# R211X.net
KiCad netlist of a schematic drawn in EAGLE
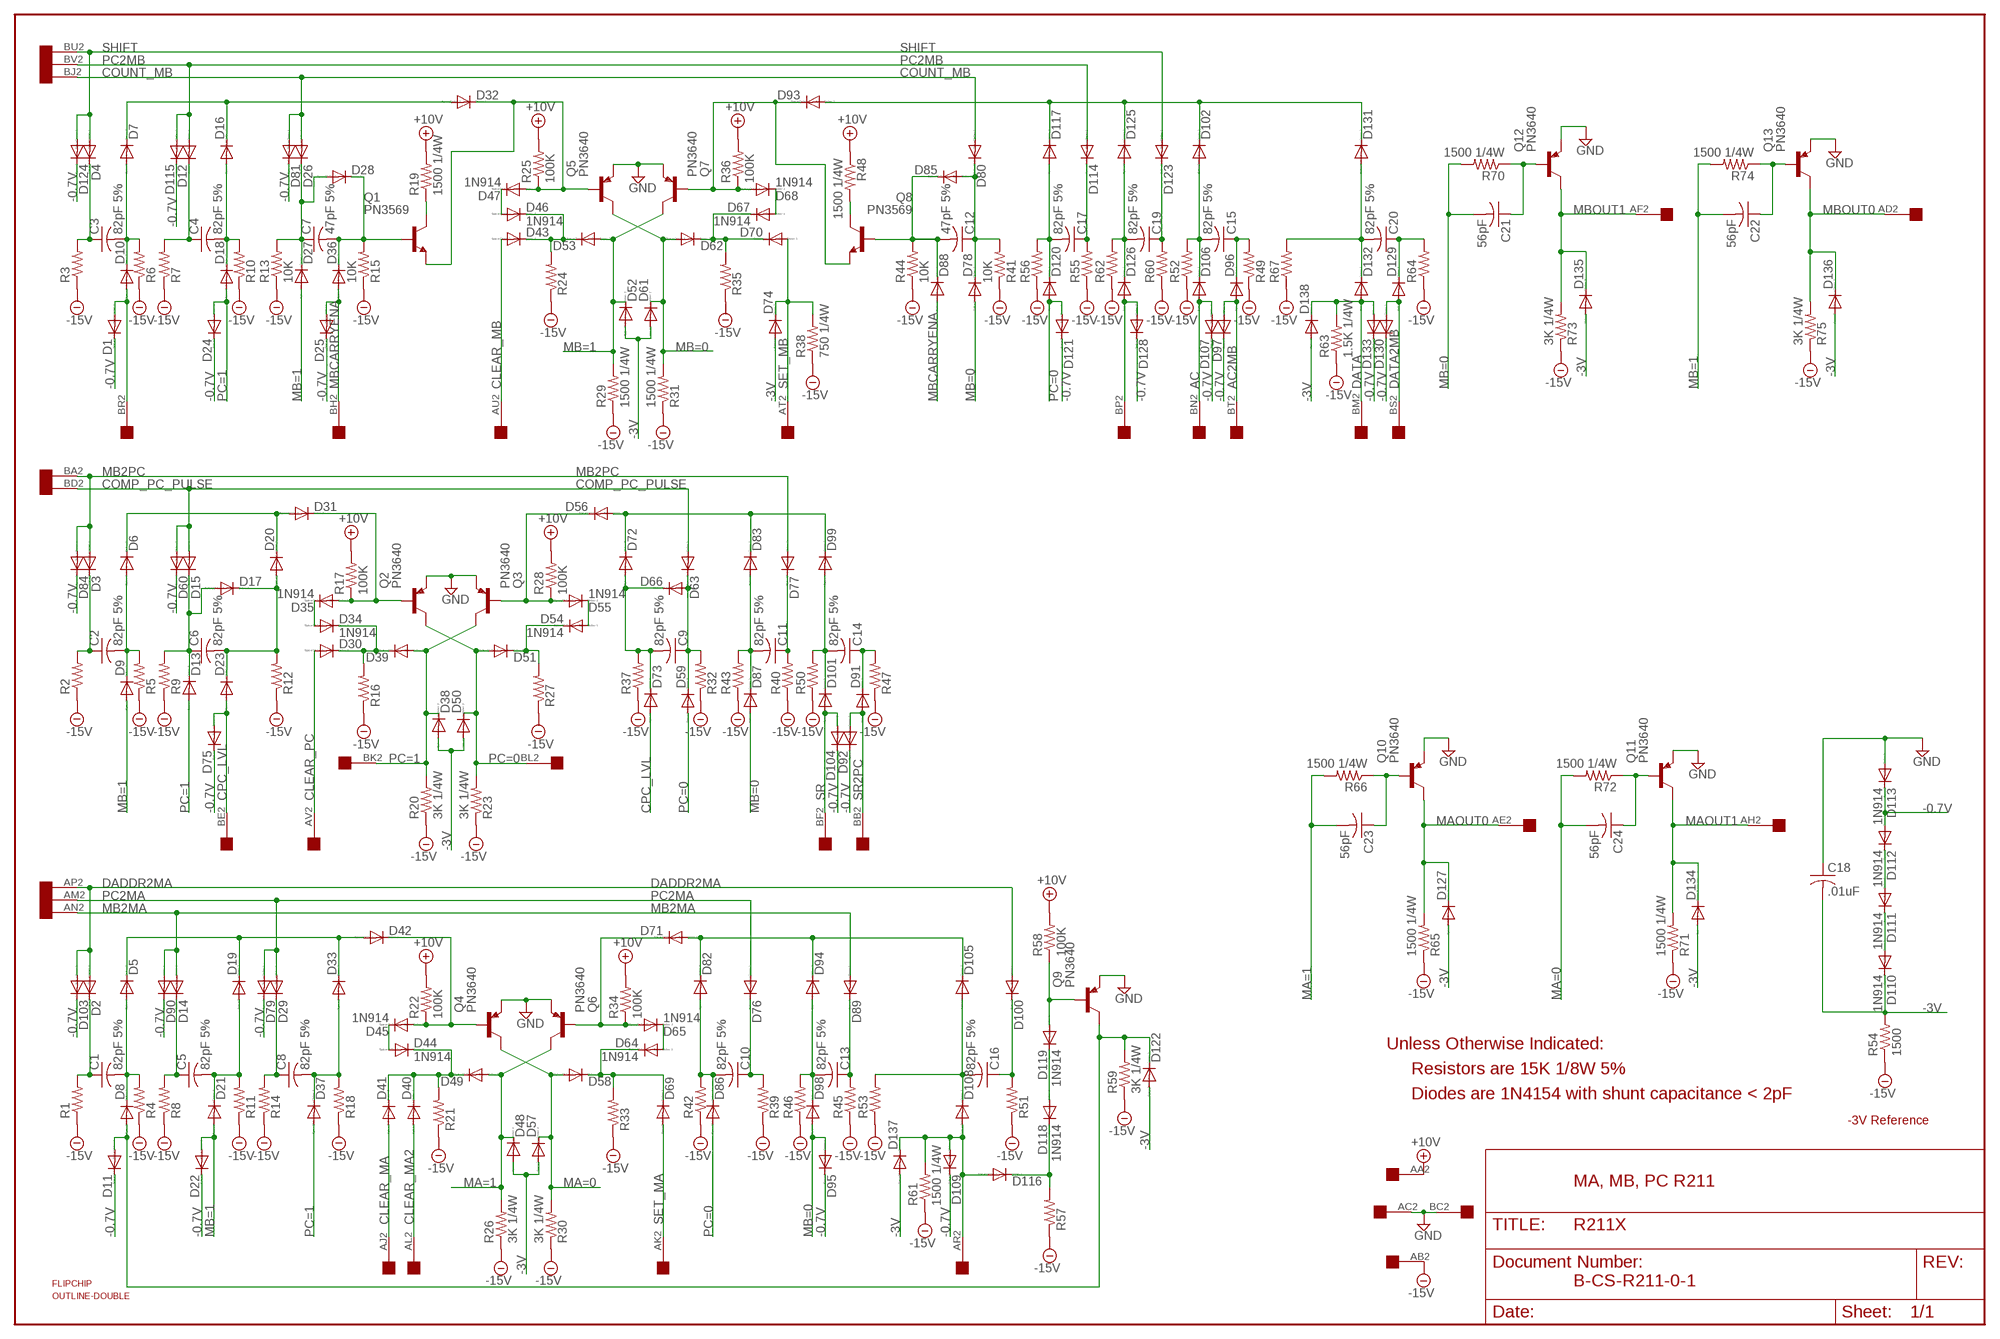
[diagram p0: schematic, sheet 1]

(export (version "E")
  (design (tool "Eeschema 10.0.6"))
  (components
    (comp (ref "C1")
      (value "82pF 5%")
      (footprint "eagle-import:C050-025X075")
      (libsource (lib "eagle-import") (part "C-US050-025X075"))
    )
    (comp (ref "C2")
      (value "82pF 5%")
      (footprint "eagle-import:C050-025X075")
      (libsource (lib "eagle-import") (part "C-US050-025X075"))
    )
    (comp (ref "C3")
      (value "82pF 5%")
      (footprint "eagle-import:C050-025X075")
      (libsource (lib "eagle-import") (part "C-US050-025X075"))
    )
    (comp (ref "C4")
      (value "82pF 5%")
      (footprint "eagle-import:C050-025X075")
      (libsource (lib "eagle-import") (part "C-US050-025X075"))
    )
    (comp (ref "C5")
      (value "82pF 5%")
      (footprint "eagle-import:C050-025X075")
      (libsource (lib "eagle-import") (part "C-US050-025X075"))
    )
    (comp (ref "C6")
      (value "82pF 5%")
      (footprint "eagle-import:C050-025X075")
      (libsource (lib "eagle-import") (part "C-US050-025X075"))
    )
    (comp (ref "C7")
      (value "47pF 5%")
      (footprint "eagle-import:C050-025X075")
      (libsource (lib "eagle-import") (part "C-US050-025X075"))
    )
    (comp (ref "C8")
      (value "82pF 5%")
      (footprint "eagle-import:C050-025X075")
      (libsource (lib "eagle-import") (part "C-US050-025X075"))
    )
    (comp (ref "C9")
      (value "82pF 5%")
      (footprint "eagle-import:C050-025X075")
      (libsource (lib "eagle-import") (part "C-US050-025X075"))
    )
    (comp (ref "C10")
      (value "82pF 5%")
      (footprint "eagle-import:C050-025X075")
      (libsource (lib "eagle-import") (part "C-US050-025X075"))
    )
    (comp (ref "C11")
      (value "82pF 5%")
      (footprint "eagle-import:C050-025X075")
      (libsource (lib "eagle-import") (part "C-US050-025X075"))
    )
    (comp (ref "C12")
      (value "47pF 5%")
      (footprint "eagle-import:C050-025X075")
      (libsource (lib "eagle-import") (part "C-US050-025X075"))
    )
    (comp (ref "C13")
      (value "82pF 5%")
      (footprint "eagle-import:C050-025X075")
      (libsource (lib "eagle-import") (part "C-US050-025X075"))
    )
    (comp (ref "C14")
      (value "82pF 5%")
      (footprint "eagle-import:C050-025X075")
      (libsource (lib "eagle-import") (part "C-US050-025X075"))
    )
    (comp (ref "C15")
      (value "82pF 5%")
      (footprint "eagle-import:C050-025X075")
      (libsource (lib "eagle-import") (part "C-US050-025X075"))
    )
    (comp (ref "C16")
      (value "82pF 5%")
      (footprint "eagle-import:C050-025X075")
      (libsource (lib "eagle-import") (part "C-US050-025X075"))
    )
    (comp (ref "C17")
      (value "82pF 5%")
      (footprint "eagle-import:C050-025X075")
      (libsource (lib "eagle-import") (part "C-US050-025X075"))
    )
    (comp (ref "C18")
      (value ".01uF")
      (footprint "eagle-import:C050-025X075")
      (libsource (lib "eagle-import") (part "C-US050-025X075"))
    )
    (comp (ref "C19")
      (value "82pF 5%")
      (footprint "eagle-import:C050-025X075")
      (libsource (lib "eagle-import") (part "C-US050-025X075"))
    )
    (comp (ref "C20")
      (value "82pF 5%")
      (footprint "eagle-import:C050-025X075")
      (libsource (lib "eagle-import") (part "C-US050-025X075"))
    )
    (comp (ref "C21")
      (value "56pF")
      (footprint "eagle-import:C050-025X075")
      (libsource (lib "eagle-import") (part "C-US050-025X075"))
    )
    (comp (ref "C22")
      (value "56pF")
      (footprint "eagle-import:C050-025X075")
      (libsource (lib "eagle-import") (part "C-US050-025X075"))
    )
    (comp (ref "C23")
      (value "56pF")
      (footprint "eagle-import:C050-025X075")
      (libsource (lib "eagle-import") (part "C-US050-025X075"))
    )
    (comp (ref "C24")
      (value "56pF")
      (footprint "eagle-import:C050-025X075")
      (libsource (lib "eagle-import") (part "C-US050-025X075"))
    )
    (comp (ref "D1")
      (value "1N4148DO35-10")
      (footprint "eagle-import:DO35-10")
      (libsource (lib "eagle-import") (part "1N4148DO35-10"))
    )
    (comp (ref "D2")
      (value "1N4148DO35-10")
      (footprint "eagle-import:DO35-10")
      (libsource (lib "eagle-import") (part "1N4148DO35-10"))
    )
    (comp (ref "D3")
      (value "1N4148DO35-10")
      (footprint "eagle-import:DO35-10")
      (libsource (lib "eagle-import") (part "1N4148DO35-10"))
    )
    (comp (ref "D4")
      (value "1N4148DO35-10")
      (footprint "eagle-import:DO35-10")
      (libsource (lib "eagle-import") (part "1N4148DO35-10"))
    )
    (comp (ref "D5")
      (value "1N4148DO35-10")
      (footprint "eagle-import:DO35-10")
      (libsource (lib "eagle-import") (part "1N4148DO35-10"))
    )
    (comp (ref "D6")
      (value "1N4148DO35-10")
      (footprint "eagle-import:DO35-10")
      (libsource (lib "eagle-import") (part "1N4148DO35-10"))
    )
    (comp (ref "D7")
      (value "1N4148DO35-10")
      (footprint "eagle-import:DO35-10")
      (libsource (lib "eagle-import") (part "1N4148DO35-10"))
    )
    (comp (ref "D8")
      (value "1N4148DO35-10")
      (footprint "eagle-import:DO35-10")
      (libsource (lib "eagle-import") (part "1N4148DO35-10"))
    )
    (comp (ref "D9")
      (value "1N4148DO35-10")
      (footprint "eagle-import:DO35-10")
      (libsource (lib "eagle-import") (part "1N4148DO35-10"))
    )
    (comp (ref "D10")
      (value "1N4148DO35-10")
      (footprint "eagle-import:DO35-10")
      (libsource (lib "eagle-import") (part "1N4148DO35-10"))
    )
    (comp (ref "D11")
      (value "1N4148DO35-10")
      (footprint "eagle-import:DO35-10")
      (libsource (lib "eagle-import") (part "1N4148DO35-10"))
    )
    (comp (ref "D12")
      (value "1N4148DO35-10")
      (footprint "eagle-import:DO35-10")
      (libsource (lib "eagle-import") (part "1N4148DO35-10"))
    )
    (comp (ref "D13")
      (value "1N4148DO35-10")
      (footprint "eagle-import:DO35-10")
      (libsource (lib "eagle-import") (part "1N4148DO35-10"))
    )
    (comp (ref "D14")
      (value "1N4148DO35-10")
      (footprint "eagle-import:DO35-10")
      (libsource (lib "eagle-import") (part "1N4148DO35-10"))
    )
    (comp (ref "D15")
      (value "1N4148DO35-10")
      (footprint "eagle-import:DO35-10")
      (libsource (lib "eagle-import") (part "1N4148DO35-10"))
    )
    (comp (ref "D16")
      (value "1N4148DO35-10")
      (footprint "eagle-import:DO35-10")
      (libsource (lib "eagle-import") (part "1N4148DO35-10"))
    )
    (comp (ref "D17")
      (value "1N4148DO35-10")
      (footprint "eagle-import:DO35-10")
      (libsource (lib "eagle-import") (part "1N4148DO35-10"))
    )
    (comp (ref "D18")
      (value "1N4148DO35-10")
      (footprint "eagle-import:DO35-10")
      (libsource (lib "eagle-import") (part "1N4148DO35-10"))
    )
    (comp (ref "D19")
      (value "1N4148DO35-10")
      (footprint "eagle-import:DO35-10")
      (libsource (lib "eagle-import") (part "1N4148DO35-10"))
    )
    (comp (ref "D20")
      (value "1N4148DO35-10")
      (footprint "eagle-import:DO35-10")
      (libsource (lib "eagle-import") (part "1N4148DO35-10"))
    )
    (comp (ref "D21")
      (value "1N4148DO35-10")
      (footprint "eagle-import:DO35-10")
      (libsource (lib "eagle-import") (part "1N4148DO35-10"))
    )
    (comp (ref "D22")
      (value "1N4148DO35-10")
      (footprint "eagle-import:DO35-10")
      (libsource (lib "eagle-import") (part "1N4148DO35-10"))
    )
    (comp (ref "D23")
      (value "1N4148DO35-10")
      (footprint "eagle-import:DO35-10")
      (libsource (lib "eagle-import") (part "1N4148DO35-10"))
    )
    (comp (ref "D24")
      (value "1N4148DO35-10")
      (footprint "eagle-import:DO35-10")
      (libsource (lib "eagle-import") (part "1N4148DO35-10"))
    )
    (comp (ref "D25")
      (value "1N4148DO35-10")
      (footprint "eagle-import:DO35-10")
      (libsource (lib "eagle-import") (part "1N4148DO35-10"))
    )
    (comp (ref "D26")
      (value "1N4148DO35-10")
      (footprint "eagle-import:DO35-10")
      (libsource (lib "eagle-import") (part "1N4148DO35-10"))
    )
    (comp (ref "D27")
      (value "1N4148DO35-10")
      (footprint "eagle-import:DO35-10")
      (libsource (lib "eagle-import") (part "1N4148DO35-10"))
    )
    (comp (ref "D28")
      (value "1N4148DO35-10")
      (footprint "eagle-import:DO35-10")
      (libsource (lib "eagle-import") (part "1N4148DO35-10"))
    )
    (comp (ref "D29")
      (value "1N4148DO35-10")
      (footprint "eagle-import:DO35-10")
      (libsource (lib "eagle-import") (part "1N4148DO35-10"))
    )
    (comp (ref "D30")
      (value "1N4148DO35-10")
      (footprint "eagle-import:DO35-10")
      (libsource (lib "eagle-import") (part "1N4148DO35-10"))
    )
    (comp (ref "D31")
      (value "1N4148DO35-10")
      (footprint "eagle-import:DO35-10")
      (libsource (lib "eagle-import") (part "1N4148DO35-10"))
    )
    (comp (ref "D32")
      (value "1N4148DO35-10")
      (footprint "eagle-import:DO35-10")
      (libsource (lib "eagle-import") (part "1N4148DO35-10"))
    )
    (comp (ref "D33")
      (value "1N4148DO35-10")
      (footprint "eagle-import:DO35-10")
      (libsource (lib "eagle-import") (part "1N4148DO35-10"))
    )
    (comp (ref "D34")
      (value "1N914")
      (footprint "eagle-import:DO35-10")
      (libsource (lib "eagle-import") (part "1N4148DO35-10"))
    )
    (comp (ref "D35")
      (value "1N914")
      (footprint "eagle-import:DO35-10")
      (libsource (lib "eagle-import") (part "1N4148DO35-10"))
    )
    (comp (ref "D36")
      (value "1N4148DO35-10")
      (footprint "eagle-import:DO35-10")
      (libsource (lib "eagle-import") (part "1N4148DO35-10"))
    )
    (comp (ref "D37")
      (value "1N4148DO35-10")
      (footprint "eagle-import:DO35-10")
      (libsource (lib "eagle-import") (part "1N4148DO35-10"))
    )
    (comp (ref "D38")
      (value "1N4148DO35-10")
      (footprint "eagle-import:DO35-10")
      (libsource (lib "eagle-import") (part "1N4148DO35-10"))
    )
    (comp (ref "D39")
      (value "1N4148DO35-10")
      (footprint "eagle-import:DO35-10")
      (libsource (lib "eagle-import") (part "1N4148DO35-10"))
    )
    (comp (ref "D40")
      (value "1N4148DO35-10")
      (footprint "eagle-import:DO35-10")
      (libsource (lib "eagle-import") (part "1N4148DO35-10"))
    )
    (comp (ref "D41")
      (value "1N4148DO35-10")
      (footprint "eagle-import:DO35-10")
      (libsource (lib "eagle-import") (part "1N4148DO35-10"))
    )
    (comp (ref "D42")
      (value "1N4148DO35-10")
      (footprint "eagle-import:DO35-10")
      (libsource (lib "eagle-import") (part "1N4148DO35-10"))
    )
    (comp (ref "D43")
      (value "1N4148DO35-10")
      (footprint "eagle-import:DO35-10")
      (libsource (lib "eagle-import") (part "1N4148DO35-10"))
    )
    (comp (ref "D44")
      (value "1N914")
      (footprint "eagle-import:DO35-10")
      (libsource (lib "eagle-import") (part "1N4148DO35-10"))
    )
    (comp (ref "D45")
      (value "1N914")
      (footprint "eagle-import:DO35-10")
      (libsource (lib "eagle-import") (part "1N4148DO35-10"))
    )
    (comp (ref "D46")
      (value "1N914")
      (footprint "eagle-import:DO35-10")
      (libsource (lib "eagle-import") (part "1N4148DO35-10"))
    )
    (comp (ref "D47")
      (value "1N914")
      (footprint "eagle-import:DO35-10")
      (libsource (lib "eagle-import") (part "1N4148DO35-10"))
    )
    (comp (ref "D48")
      (value "1N4148DO35-10")
      (footprint "eagle-import:DO35-10")
      (libsource (lib "eagle-import") (part "1N4148DO35-10"))
    )
    (comp (ref "D49")
      (value "1N4148DO35-10")
      (footprint "eagle-import:DO35-10")
      (libsource (lib "eagle-import") (part "1N4148DO35-10"))
    )
    (comp (ref "D50")
      (value "1N4148DO35-10")
      (footprint "eagle-import:DO35-10")
      (libsource (lib "eagle-import") (part "1N4148DO35-10"))
    )
    (comp (ref "D51")
      (value "1N4148DO35-10")
      (footprint "eagle-import:DO35-10")
      (libsource (lib "eagle-import") (part "1N4148DO35-10"))
    )
    (comp (ref "D52")
      (value "1N4148DO35-10")
      (footprint "eagle-import:DO35-10")
      (libsource (lib "eagle-import") (part "1N4148DO35-10"))
    )
    (comp (ref "D53")
      (value "1N4148DO35-10")
      (footprint "eagle-import:DO35-10")
      (libsource (lib "eagle-import") (part "1N4148DO35-10"))
    )
    (comp (ref "D54")
      (value "1N914")
      (footprint "eagle-import:DO35-10")
      (libsource (lib "eagle-import") (part "1N4148DO35-10"))
    )
    (comp (ref "D55")
      (value "1N914")
      (footprint "eagle-import:DO35-10")
      (libsource (lib "eagle-import") (part "1N4148DO35-10"))
    )
    (comp (ref "D56")
      (value "1N4148DO35-10")
      (footprint "eagle-import:DO35-10")
      (libsource (lib "eagle-import") (part "1N4148DO35-10"))
    )
    (comp (ref "D57")
      (value "1N4148DO35-10")
      (footprint "eagle-import:DO35-10")
      (libsource (lib "eagle-import") (part "1N4148DO35-10"))
    )
    (comp (ref "D58")
      (value "1N4148DO35-10")
      (footprint "eagle-import:DO35-10")
      (libsource (lib "eagle-import") (part "1N4148DO35-10"))
    )
    (comp (ref "D59")
      (value "1N4148DO35-10")
      (footprint "eagle-import:DO35-10")
      (libsource (lib "eagle-import") (part "1N4148DO35-10"))
    )
    (comp (ref "D60")
      (value "1N4148DO35-10")
      (footprint "eagle-import:DO35-10")
      (libsource (lib "eagle-import") (part "1N4148DO35-10"))
    )
    (comp (ref "D61")
      (value "1N4148DO35-10")
      (footprint "eagle-import:DO35-10")
      (libsource (lib "eagle-import") (part "1N4148DO35-10"))
    )
    (comp (ref "D62")
      (value "1N4148DO35-10")
      (footprint "eagle-import:DO35-10")
      (libsource (lib "eagle-import") (part "1N4148DO35-10"))
    )
    (comp (ref "D63")
      (value "1N4148DO35-10")
      (footprint "eagle-import:DO35-10")
      (libsource (lib "eagle-import") (part "1N4148DO35-10"))
    )
    (comp (ref "D64")
      (value "1N914")
      (footprint "eagle-import:DO35-10")
      (libsource (lib "eagle-import") (part "1N4148DO35-10"))
    )
    (comp (ref "D65")
      (value "1N914")
      (footprint "eagle-import:DO35-10")
      (libsource (lib "eagle-import") (part "1N4148DO35-10"))
    )
    (comp (ref "D66")
      (value "1N4148DO35-10")
      (footprint "eagle-import:DO35-10")
      (libsource (lib "eagle-import") (part "1N4148DO35-10"))
    )
    (comp (ref "D67")
      (value "1N914")
      (footprint "eagle-import:DO35-10")
      (libsource (lib "eagle-import") (part "1N4148DO35-10"))
    )
    (comp (ref "D68")
      (value "1N914")
      (footprint "eagle-import:DO35-10")
      (libsource (lib "eagle-import") (part "1N4148DO35-10"))
    )
    (comp (ref "D69")
      (value "1N4148DO35-10")
      (footprint "eagle-import:DO35-10")
      (libsource (lib "eagle-import") (part "1N4148DO35-10"))
    )
    (comp (ref "D70")
      (value "1N4148DO35-10")
      (footprint "eagle-import:DO35-10")
      (libsource (lib "eagle-import") (part "1N4148DO35-10"))
    )
    (comp (ref "D71")
      (value "1N4148DO35-10")
      (footprint "eagle-import:DO35-10")
      (libsource (lib "eagle-import") (part "1N4148DO35-10"))
    )
    (comp (ref "D72")
      (value "1N4148DO35-10")
      (footprint "eagle-import:DO35-10")
      (libsource (lib "eagle-import") (part "1N4148DO35-10"))
    )
    (comp (ref "D73")
      (value "1N4148DO35-10")
      (footprint "eagle-import:DO35-10")
      (libsource (lib "eagle-import") (part "1N4148DO35-10"))
    )
    (comp (ref "D74")
      (value "1N4148DO35-10")
      (footprint "eagle-import:DO35-10")
      (libsource (lib "eagle-import") (part "1N4148DO35-10"))
    )
    (comp (ref "D75")
      (value "1N4148DO35-10")
      (footprint "eagle-import:DO35-10")
      (libsource (lib "eagle-import") (part "1N4148DO35-10"))
    )
    (comp (ref "D76")
      (value "1N4148DO35-10")
      (footprint "eagle-import:DO35-10")
      (libsource (lib "eagle-import") (part "1N4148DO35-10"))
    )
    (comp (ref "D77")
      (value "1N4148DO35-10")
      (footprint "eagle-import:DO35-10")
      (libsource (lib "eagle-import") (part "1N4148DO35-10"))
    )
    (comp (ref "D78")
      (value "1N4148DO35-10")
      (footprint "eagle-import:DO35-10")
      (libsource (lib "eagle-import") (part "1N4148DO35-10"))
    )
    (comp (ref "D79")
      (value "1N4148DO35-10")
      (footprint "eagle-import:DO35-10")
      (libsource (lib "eagle-import") (part "1N4148DO35-10"))
    )
    (comp (ref "D80")
      (value "1N4148DO35-10")
      (footprint "eagle-import:DO35-10")
      (libsource (lib "eagle-import") (part "1N4148DO35-10"))
    )
    (comp (ref "D81")
      (value "1N4148DO35-10")
      (footprint "eagle-import:DO35-10")
      (libsource (lib "eagle-import") (part "1N4148DO35-10"))
    )
    (comp (ref "D82")
      (value "1N4148DO35-10")
      (footprint "eagle-import:DO35-10")
      (libsource (lib "eagle-import") (part "1N4148DO35-10"))
    )
    (comp (ref "D83")
      (value "1N4148DO35-10")
      (footprint "eagle-import:DO35-10")
      (libsource (lib "eagle-import") (part "1N4148DO35-10"))
    )
    (comp (ref "D84")
      (value "1N4148DO35-10")
      (footprint "eagle-import:DO35-10")
      (libsource (lib "eagle-import") (part "1N4148DO35-10"))
    )
    (comp (ref "D85")
      (value "1N4148DO35-10")
      (footprint "eagle-import:DO35-10")
      (libsource (lib "eagle-import") (part "1N4148DO35-10"))
    )
    (comp (ref "D86")
      (value "1N4148DO35-10")
      (footprint "eagle-import:DO35-10")
      (libsource (lib "eagle-import") (part "1N4148DO35-10"))
    )
    (comp (ref "D87")
      (value "1N4148DO35-10")
      (footprint "eagle-import:DO35-10")
      (libsource (lib "eagle-import") (part "1N4148DO35-10"))
    )
    (comp (ref "D88")
      (value "1N4148DO35-10")
      (footprint "eagle-import:DO35-10")
      (libsource (lib "eagle-import") (part "1N4148DO35-10"))
    )
    (comp (ref "D89")
      (value "1N4148DO35-10")
      (footprint "eagle-import:DO35-10")
      (libsource (lib "eagle-import") (part "1N4148DO35-10"))
    )
    (comp (ref "D90")
      (value "1N4148DO35-10")
      (footprint "eagle-import:DO35-10")
      (libsource (lib "eagle-import") (part "1N4148DO35-10"))
    )
    (comp (ref "D91")
      (value "1N4148DO35-10")
      (footprint "eagle-import:DO35-10")
      (libsource (lib "eagle-import") (part "1N4148DO35-10"))
    )
    (comp (ref "D92")
      (value "1N4148DO35-10")
      (footprint "eagle-import:DO35-10")
      (libsource (lib "eagle-import") (part "1N4148DO35-10"))
    )
    (comp (ref "D93")
      (value "1N4148DO35-10")
      (footprint "eagle-import:DO35-10")
      (libsource (lib "eagle-import") (part "1N4148DO35-10"))
    )
    (comp (ref "D94")
      (value "1N4148DO35-10")
      (footprint "eagle-import:DO35-10")
      (libsource (lib "eagle-import") (part "1N4148DO35-10"))
    )
    (comp (ref "D95")
      (value "1N4148DO35-10")
      (footprint "eagle-import:DO35-10")
      (libsource (lib "eagle-import") (part "1N4148DO35-10"))
    )
    (comp (ref "D96")
      (value "1N4148DO35-10")
      (footprint "eagle-import:DO35-10")
      (libsource (lib "eagle-import") (part "1N4148DO35-10"))
    )
    (comp (ref "D97")
      (value "1N4148DO35-10")
      (footprint "eagle-import:DO35-10")
      (libsource (lib "eagle-import") (part "1N4148DO35-10"))
    )
    (comp (ref "D98")
      (value "1N4148DO35-10")
      (footprint "eagle-import:DO35-10")
      (libsource (lib "eagle-import") (part "1N4148DO35-10"))
    )
    (comp (ref "D99")
      (value "1N4148DO35-10")
      (footprint "eagle-import:DO35-10")
      (libsource (lib "eagle-import") (part "1N4148DO35-10"))
    )
    (comp (ref "D100")
      (value "1N4148DO35-10")
      (footprint "eagle-import:DO35-10")
      (libsource (lib "eagle-import") (part "1N4148DO35-10"))
    )
    (comp (ref "D101")
      (value "1N4148DO35-10")
      (footprint "eagle-import:DO35-10")
      (libsource (lib "eagle-import") (part "1N4148DO35-10"))
    )
    (comp (ref "D102")
      (value "1N4148DO35-10")
      (footprint "eagle-import:DO35-10")
      (libsource (lib "eagle-import") (part "1N4148DO35-10"))
    )
    (comp (ref "D103")
      (value "1N4148DO35-10")
      (footprint "eagle-import:DO35-10")
      (libsource (lib "eagle-import") (part "1N4148DO35-10"))
    )
    (comp (ref "D104")
      (value "1N4148DO35-10")
      (footprint "eagle-import:DO35-10")
      (libsource (lib "eagle-import") (part "1N4148DO35-10"))
    )
    (comp (ref "D105")
      (value "1N4148DO35-10")
      (footprint "eagle-import:DO35-10")
      (libsource (lib "eagle-import") (part "1N4148DO35-10"))
    )
    (comp (ref "D106")
      (value "1N4148DO35-10")
      (footprint "eagle-import:DO35-10")
      (libsource (lib "eagle-import") (part "1N4148DO35-10"))
    )
    (comp (ref "D107")
      (value "1N4148DO35-10")
      (footprint "eagle-import:DO35-10")
      (libsource (lib "eagle-import") (part "1N4148DO35-10"))
    )
    (comp (ref "D108")
      (value "1N4148DO35-10")
      (footprint "eagle-import:DO35-10")
      (libsource (lib "eagle-import") (part "1N4148DO35-10"))
    )
    (comp (ref "D109")
      (value "1N4148DO35-10")
      (footprint "eagle-import:DO35-10")
      (libsource (lib "eagle-import") (part "1N4148DO35-10"))
    )
    (comp (ref "D110")
      (value "1N914")
      (footprint "eagle-import:DO35-10")
      (libsource (lib "eagle-import") (part "1N4148DO35-10"))
    )
    (comp (ref "D111")
      (value "1N914")
      (footprint "eagle-import:DO35-10")
      (libsource (lib "eagle-import") (part "1N4148DO35-10"))
    )
    (comp (ref "D112")
      (value "1N914")
      (footprint "eagle-import:DO35-10")
      (libsource (lib "eagle-import") (part "1N4148DO35-10"))
    )
    (comp (ref "D113")
      (value "1N914")
      (footprint "eagle-import:DO35-10")
      (libsource (lib "eagle-import") (part "1N4148DO35-10"))
    )
    (comp (ref "D114")
      (value "1N4148DO35-10")
      (footprint "eagle-import:DO35-10")
      (libsource (lib "eagle-import") (part "1N4148DO35-10"))
    )
    (comp (ref "D115")
      (value "1N4148DO35-10")
      (footprint "eagle-import:DO35-10")
      (libsource (lib "eagle-import") (part "1N4148DO35-10"))
    )
    (comp (ref "D116")
      (value "1N4148DO35-10")
      (footprint "eagle-import:DO35-10")
      (libsource (lib "eagle-import") (part "1N4148DO35-10"))
    )
    (comp (ref "D117")
      (value "1N4148DO35-10")
      (footprint "eagle-import:DO35-10")
      (libsource (lib "eagle-import") (part "1N4148DO35-10"))
    )
    (comp (ref "D118")
      (value "1N914")
      (footprint "eagle-import:DO35-10")
      (libsource (lib "eagle-import") (part "1N4148DO35-10"))
    )
    (comp (ref "D119")
      (value "1N914")
      (footprint "eagle-import:DO35-10")
      (libsource (lib "eagle-import") (part "1N4148DO35-10"))
    )
    (comp (ref "D120")
      (value "1N4148DO35-10")
      (footprint "eagle-import:DO35-10")
      (libsource (lib "eagle-import") (part "1N4148DO35-10"))
    )
    (comp (ref "D121")
      (value "1N4148DO35-10")
      (footprint "eagle-import:DO35-10")
      (libsource (lib "eagle-import") (part "1N4148DO35-10"))
    )
    (comp (ref "D122")
      (value "1N4148DO35-10")
      (footprint "eagle-import:DO35-10")
      (libsource (lib "eagle-import") (part "1N4148DO35-10"))
    )
    (comp (ref "D123")
      (value "1N4148DO35-10")
      (footprint "eagle-import:DO35-10")
      (libsource (lib "eagle-import") (part "1N4148DO35-10"))
    )
    (comp (ref "D124")
      (value "1N4148DO35-10")
      (footprint "eagle-import:DO35-10")
      (libsource (lib "eagle-import") (part "1N4148DO35-10"))
    )
    (comp (ref "D125")
      (value "1N4148DO35-10")
      (footprint "eagle-import:DO35-10")
      (libsource (lib "eagle-import") (part "1N4148DO35-10"))
    )
    (comp (ref "D126")
      (value "1N4148DO35-10")
      (footprint "eagle-import:DO35-10")
      (libsource (lib "eagle-import") (part "1N4148DO35-10"))
    )
    (comp (ref "D127")
      (value "1N4148DO35-10")
      (footprint "eagle-import:DO35-10")
      (libsource (lib "eagle-import") (part "1N4148DO35-10"))
    )
    (comp (ref "D128")
      (value "1N4148DO35-10")
      (footprint "eagle-import:DO35-10")
      (libsource (lib "eagle-import") (part "1N4148DO35-10"))
    )
    (comp (ref "D129")
      (value "1N4148DO35-10")
      (footprint "eagle-import:DO35-10")
      (libsource (lib "eagle-import") (part "1N4148DO35-10"))
    )
    (comp (ref "D130")
      (value "1N4148DO35-10")
      (footprint "eagle-import:DO35-10")
      (libsource (lib "eagle-import") (part "1N4148DO35-10"))
    )
    (comp (ref "D131")
      (value "1N4148DO35-10")
      (footprint "eagle-import:DO35-10")
      (libsource (lib "eagle-import") (part "1N4148DO35-10"))
    )
    (comp (ref "D132")
      (value "1N4148DO35-10")
      (footprint "eagle-import:DO35-10")
      (libsource (lib "eagle-import") (part "1N4148DO35-10"))
    )
    (comp (ref "D133")
      (value "1N4148DO35-10")
      (footprint "eagle-import:DO35-10")
      (libsource (lib "eagle-import") (part "1N4148DO35-10"))
    )
    (comp (ref "D134")
      (value "1N4148DO35-10")
      (footprint "eagle-import:DO35-10")
      (libsource (lib "eagle-import") (part "1N4148DO35-10"))
    )
    (comp (ref "D135")
      (value "1N4148DO35-10")
      (footprint "eagle-import:DO35-10")
      (libsource (lib "eagle-import") (part "1N4148DO35-10"))
    )
    (comp (ref "D136")
      (value "1N4148DO35-10")
      (footprint "eagle-import:DO35-10")
      (libsource (lib "eagle-import") (part "1N4148DO35-10"))
    )
    (comp (ref "D137")
      (value "1N4148DO35-10")
      (footprint "eagle-import:DO35-10")
      (libsource (lib "eagle-import") (part "1N4148DO35-10"))
    )
    (comp (ref "D138")
      (value "1N4148DO35-10")
      (footprint "eagle-import:DO35-10")
      (libsource (lib "eagle-import") (part "1N4148DO35-10"))
    )
    (comp (ref "Q1")
      (value "PN3569")
      (footprint "eagle-import:TO5")
      (libsource (lib "eagle-import") (part "2N2102"))
    )
    (comp (ref "Q2")
      (value "PN3640")
      (footprint "eagle-import:TO39")
      (libsource (lib "eagle-import") (part "2N3637"))
    )
    (comp (ref "Q3")
      (value "PN3640")
      (footprint "eagle-import:TO39")
      (libsource (lib "eagle-import") (part "2N3637"))
    )
    (comp (ref "Q4")
      (value "PN3640")
      (footprint "eagle-import:TO39")
      (libsource (lib "eagle-import") (part "2N3637"))
    )
    (comp (ref "Q5")
      (value "PN3640")
      (footprint "eagle-import:TO39")
      (libsource (lib "eagle-import") (part "2N3637"))
    )
    (comp (ref "Q6")
      (value "PN3640")
      (footprint "eagle-import:TO39")
      (libsource (lib "eagle-import") (part "2N3637"))
    )
    (comp (ref "Q7")
      (value "PN3640")
      (footprint "eagle-import:TO39")
      (libsource (lib "eagle-import") (part "2N3637"))
    )
    (comp (ref "Q8")
      (value "PN3569")
      (footprint "eagle-import:TO5")
      (libsource (lib "eagle-import") (part "2N2102"))
    )
    (comp (ref "Q9")
      (value "PN3640")
      (footprint "eagle-import:TO39")
      (libsource (lib "eagle-import") (part "2N3637"))
    )
    (comp (ref "Q10")
      (value "PN3640")
      (footprint "eagle-import:TO39")
      (libsource (lib "eagle-import") (part "2N3637"))
    )
    (comp (ref "Q11")
      (value "PN3640")
      (footprint "eagle-import:TO39")
      (libsource (lib "eagle-import") (part "2N3637"))
    )
    (comp (ref "Q12")
      (value "PN3640")
      (footprint "eagle-import:TO39")
      (libsource (lib "eagle-import") (part "2N3637"))
    )
    (comp (ref "Q13")
      (value "PN3640")
      (footprint "eagle-import:TO39")
      (libsource (lib "eagle-import") (part "2N3637"))
    )
    (comp (ref "R1")
      (value "R-US_0207/10")
      (footprint "eagle-import:0207_10")
      (libsource (lib "eagle-import") (part "R-US_0207/10"))
    )
    (comp (ref "R2")
      (value "R-US_0207/10")
      (footprint "eagle-import:0207_10")
      (libsource (lib "eagle-import") (part "R-US_0207/10"))
    )
    (comp (ref "R3")
      (value "R-US_0207/10")
      (footprint "eagle-import:0207_10")
      (libsource (lib "eagle-import") (part "R-US_0207/10"))
    )
    (comp (ref "R4")
      (value "R-US_0207/10")
      (footprint "eagle-import:0207_10")
      (libsource (lib "eagle-import") (part "R-US_0207/10"))
    )
    (comp (ref "R5")
      (value "R-US_0207/10")
      (footprint "eagle-import:0207_10")
      (libsource (lib "eagle-import") (part "R-US_0207/10"))
    )
    (comp (ref "R6")
      (value "R-US_0207/10")
      (footprint "eagle-import:0207_10")
      (libsource (lib "eagle-import") (part "R-US_0207/10"))
    )
    (comp (ref "R7")
      (value "R-US_0207/10")
      (footprint "eagle-import:0207_10")
      (libsource (lib "eagle-import") (part "R-US_0207/10"))
    )
    (comp (ref "R8")
      (value "R-US_0207/10")
      (footprint "eagle-import:0207_10")
      (libsource (lib "eagle-import") (part "R-US_0207/10"))
    )
    (comp (ref "R9")
      (value "R-US_0207/10")
      (footprint "eagle-import:0207_10")
      (libsource (lib "eagle-import") (part "R-US_0207/10"))
    )
    (comp (ref "R10")
      (value "R-US_0207/10")
      (footprint "eagle-import:0207_10")
      (libsource (lib "eagle-import") (part "R-US_0207/10"))
    )
    (comp (ref "R11")
      (value "R-US_0207/10")
      (footprint "eagle-import:0207_10")
      (libsource (lib "eagle-import") (part "R-US_0207/10"))
    )
    (comp (ref "R12")
      (value "R-US_0207/10")
      (footprint "eagle-import:0207_10")
      (libsource (lib "eagle-import") (part "R-US_0207/10"))
    )
    (comp (ref "R13")
      (value "10K")
      (footprint "eagle-import:0207_10")
      (libsource (lib "eagle-import") (part "R-US_0207/10"))
    )
    (comp (ref "R14")
      (value "R-US_0207/10")
      (footprint "eagle-import:0207_10")
      (libsource (lib "eagle-import") (part "R-US_0207/10"))
    )
    (comp (ref "R15")
      (value "10K")
      (footprint "eagle-import:0207_10")
      (libsource (lib "eagle-import") (part "R-US_0207/10"))
    )
    (comp (ref "R16")
      (value "R-US_0207/10")
      (footprint "eagle-import:0207_10")
      (libsource (lib "eagle-import") (part "R-US_0207/10"))
    )
    (comp (ref "R17")
      (value "100K")
      (footprint "eagle-import:0207_10")
      (libsource (lib "eagle-import") (part "R-US_0207/10"))
    )
    (comp (ref "R18")
      (value "R-US_0207/10")
      (footprint "eagle-import:0207_10")
      (libsource (lib "eagle-import") (part "R-US_0207/10"))
    )
    (comp (ref "R19")
      (value "1500 1/4W")
      (footprint "eagle-import:0207_10")
      (libsource (lib "eagle-import") (part "R-US_0207/10"))
    )
    (comp (ref "R20")
      (value "3K 1/4W")
      (footprint "eagle-import:0207_10")
      (libsource (lib "eagle-import") (part "R-US_0207/10"))
    )
    (comp (ref "R21")
      (value "R-US_0207/10")
      (footprint "eagle-import:0207_10")
      (libsource (lib "eagle-import") (part "R-US_0207/10"))
    )
    (comp (ref "R22")
      (value "100K")
      (footprint "eagle-import:0207_10")
      (libsource (lib "eagle-import") (part "R-US_0207/10"))
    )
    (comp (ref "R23")
      (value "3K 1/4W")
      (footprint "eagle-import:0207_10")
      (libsource (lib "eagle-import") (part "R-US_0207/10"))
    )
    (comp (ref "R24")
      (value "R-US_0207/10")
      (footprint "eagle-import:0207_10")
      (libsource (lib "eagle-import") (part "R-US_0207/10"))
    )
    (comp (ref "R25")
      (value "100K")
      (footprint "eagle-import:0207_10")
      (libsource (lib "eagle-import") (part "R-US_0207/10"))
    )
    (comp (ref "R26")
      (value "3K 1/4W")
      (footprint "eagle-import:0207_10")
      (libsource (lib "eagle-import") (part "R-US_0207/10"))
    )
    (comp (ref "R27")
      (value "R-US_0207/10")
      (footprint "eagle-import:0207_10")
      (libsource (lib "eagle-import") (part "R-US_0207/10"))
    )
    (comp (ref "R28")
      (value "100K")
      (footprint "eagle-import:0207_10")
      (libsource (lib "eagle-import") (part "R-US_0207/10"))
    )
    (comp (ref "R29")
      (value "1500 1/4W")
      (footprint "eagle-import:0207_10")
      (libsource (lib "eagle-import") (part "R-US_0207/10"))
    )
    (comp (ref "R30")
      (value "3K 1/4W")
      (footprint "eagle-import:0207_10")
      (libsource (lib "eagle-import") (part "R-US_0207/10"))
    )
    (comp (ref "R31")
      (value "1500 1/4W")
      (footprint "eagle-import:0207_10")
      (libsource (lib "eagle-import") (part "R-US_0207/10"))
    )
    (comp (ref "R32")
      (value "R-US_0207/10")
      (footprint "eagle-import:0207_10")
      (libsource (lib "eagle-import") (part "R-US_0207/10"))
    )
    (comp (ref "R33")
      (value "R-US_0207/10")
      (footprint "eagle-import:0207_10")
      (libsource (lib "eagle-import") (part "R-US_0207/10"))
    )
    (comp (ref "R34")
      (value "100K")
      (footprint "eagle-import:0207_10")
      (libsource (lib "eagle-import") (part "R-US_0207/10"))
    )
    (comp (ref "R35")
      (value "R-US_0207/10")
      (footprint "eagle-import:0207_10")
      (libsource (lib "eagle-import") (part "R-US_0207/10"))
    )
    (comp (ref "R36")
      (value "100K")
      (footprint "eagle-import:0207_10")
      (libsource (lib "eagle-import") (part "R-US_0207/10"))
    )
    (comp (ref "R37")
      (value "R-US_0207/10")
      (footprint "eagle-import:0207_10")
      (libsource (lib "eagle-import") (part "R-US_0207/10"))
    )
    (comp (ref "R38")
      (value "750 1/4W")
      (footprint "eagle-import:0207_10")
      (libsource (lib "eagle-import") (part "R-US_0207/10"))
    )
    (comp (ref "R39")
      (value "R-US_0207/10")
      (footprint "eagle-import:0207_10")
      (libsource (lib "eagle-import") (part "R-US_0207/10"))
    )
    (comp (ref "R40")
      (value "R-US_0207/10")
      (footprint "eagle-import:0207_10")
      (libsource (lib "eagle-import") (part "R-US_0207/10"))
    )
    (comp (ref "R41")
      (value "10K")
      (footprint "eagle-import:0207_10")
      (libsource (lib "eagle-import") (part "R-US_0207/10"))
    )
    (comp (ref "R42")
      (value "R-US_0207/10")
      (footprint "eagle-import:0207_10")
      (libsource (lib "eagle-import") (part "R-US_0207/10"))
    )
    (comp (ref "R43")
      (value "R-US_0207/10")
      (footprint "eagle-import:0207_10")
      (libsource (lib "eagle-import") (part "R-US_0207/10"))
    )
    (comp (ref "R44")
      (value "10K")
      (footprint "eagle-import:0207_10")
      (libsource (lib "eagle-import") (part "R-US_0207/10"))
    )
    (comp (ref "R45")
      (value "R-US_0207/10")
      (footprint "eagle-import:0207_10")
      (libsource (lib "eagle-import") (part "R-US_0207/10"))
    )
    (comp (ref "R46")
      (value "R-US_0207/10")
      (footprint "eagle-import:0207_10")
      (libsource (lib "eagle-import") (part "R-US_0207/10"))
    )
    (comp (ref "R47")
      (value "R-US_0207/10")
      (footprint "eagle-import:0207_10")
      (libsource (lib "eagle-import") (part "R-US_0207/10"))
    )
    (comp (ref "R48")
      (value "1500 1/4W")
      (footprint "eagle-import:0207_10")
      (libsource (lib "eagle-import") (part "R-US_0207/10"))
    )
    (comp (ref "R49")
      (value "R-US_0207/10")
      (footprint "eagle-import:0207_10")
      (libsource (lib "eagle-import") (part "R-US_0207/10"))
    )
    (comp (ref "R50")
      (value "R-US_0207/10")
      (footprint "eagle-import:0207_10")
      (libsource (lib "eagle-import") (part "R-US_0207/10"))
    )
    (comp (ref "R51")
      (value "R-US_0207/10")
      (footprint "eagle-import:0207_10")
      (libsource (lib "eagle-import") (part "R-US_0207/10"))
    )
    (comp (ref "R52")
      (value "R-US_0207/10")
      (footprint "eagle-import:0207_10")
      (libsource (lib "eagle-import") (part "R-US_0207/10"))
    )
    (comp (ref "R53")
      (value "R-US_0207/10")
      (footprint "eagle-import:0207_10")
      (libsource (lib "eagle-import") (part "R-US_0207/10"))
    )
    (comp (ref "R54")
      (value "1500")
      (footprint "eagle-import:0207_10")
      (libsource (lib "eagle-import") (part "R-US_0207/10"))
    )
    (comp (ref "R55")
      (value "R-US_0207/10")
      (footprint "eagle-import:0207_10")
      (libsource (lib "eagle-import") (part "R-US_0207/10"))
    )
    (comp (ref "R56")
      (value "R-US_0207/10")
      (footprint "eagle-import:0207_10")
      (libsource (lib "eagle-import") (part "R-US_0207/10"))
    )
    (comp (ref "R57")
      (value "R-US_0207/10")
      (footprint "eagle-import:0207_10")
      (libsource (lib "eagle-import") (part "R-US_0207/10"))
    )
    (comp (ref "R58")
      (value "100K")
      (footprint "eagle-import:0207_10")
      (libsource (lib "eagle-import") (part "R-US_0207/10"))
    )
    (comp (ref "R59")
      (value "3K 1/4W")
      (footprint "eagle-import:0207_10")
      (libsource (lib "eagle-import") (part "R-US_0207/10"))
    )
    (comp (ref "R60")
      (value "R-US_0207/10")
      (footprint "eagle-import:0207_10")
      (libsource (lib "eagle-import") (part "R-US_0207/10"))
    )
    (comp (ref "R61")
      (value "1500 1/4W")
      (footprint "eagle-import:0207_10")
      (libsource (lib "eagle-import") (part "R-US_0207/10"))
    )
    (comp (ref "R62")
      (value "R-US_0207/10")
      (footprint "eagle-import:0207_10")
      (libsource (lib "eagle-import") (part "R-US_0207/10"))
    )
    (comp (ref "R63")
      (value "1.5K 1/4W")
      (footprint "eagle-import:0207_10")
      (libsource (lib "eagle-import") (part "R-US_0207/10"))
    )
    (comp (ref "R64")
      (value "R-US_0207/10")
      (footprint "eagle-import:0207_10")
      (libsource (lib "eagle-import") (part "R-US_0207/10"))
    )
    (comp (ref "R65")
      (value "1500 1/4W")
      (footprint "eagle-import:0207_10")
      (libsource (lib "eagle-import") (part "R-US_0207/10"))
    )
    (comp (ref "R66")
      (value "1500 1/4W")
      (footprint "eagle-import:0207_10")
      (libsource (lib "eagle-import") (part "R-US_0207/10"))
    )
    (comp (ref "R67")
      (value "R-US_0207/10")
      (footprint "eagle-import:0207_10")
      (libsource (lib "eagle-import") (part "R-US_0207/10"))
    )
    (comp (ref "R70")
      (value "1500 1/4W")
      (footprint "eagle-import:0207_10")
      (libsource (lib "eagle-import") (part "R-US_0207/10"))
    )
    (comp (ref "R71")
      (value "1500 1/4W")
      (footprint "eagle-import:0207_10")
      (libsource (lib "eagle-import") (part "R-US_0207/10"))
    )
    (comp (ref "R72")
      (value "1500 1/4W")
      (footprint "eagle-import:0207_10")
      (libsource (lib "eagle-import") (part "R-US_0207/10"))
    )
    (comp (ref "R73")
      (value "3K 1/4W")
      (footprint "eagle-import:0207_10")
      (libsource (lib "eagle-import") (part "R-US_0207/10"))
    )
    (comp (ref "R74")
      (value "1500 1/4W")
      (footprint "eagle-import:0207_10")
      (libsource (lib "eagle-import") (part "R-US_0207/10"))
    )
    (comp (ref "R75")
      (value "3K 1/4W")
      (footprint "eagle-import:0207_10")
      (libsource (lib "eagle-import") (part "R-US_0207/10"))
    )
    (comp (ref "U$1")
      (value "DOUBLE")
      (footprint "eagle-import:EDGE-CON4")
      (libsource (lib "eagle-import") (part "DOUBLE"))
    )
    (comp (ref "U$2")
      (value "FLIPCHIP")
      (footprint "eagle-import:FLIPCHIP")
      (libsource (lib "eagle-import") (part "FLIPCHIP"))
    )
    (comp (ref "U$3")
      (value "OUTLINE-DOUBLE")
      (footprint "eagle-import:DOUBLE")
      (libsource (lib "eagle-import") (part "OUTLINE-DOUBLE"))
    )
  )
  (nets
    (net (code "1") (name "+10V") (class "Default")
      (node (ref "R17") (pin "2") (pinfunction "2_2") (pintype "passive"))
      (node (ref "R19") (pin "2") (pinfunction "2_2") (pintype "passive"))
      (node (ref "R22") (pin "2") (pinfunction "2_2") (pintype "passive"))
      (node (ref "R25") (pin "2") (pinfunction "2_2") (pintype "passive"))
      (node (ref "R28") (pin "2") (pinfunction "2_2") (pintype "passive"))
      (node (ref "R34") (pin "2") (pinfunction "2_2") (pintype "passive"))
      (node (ref "R36") (pin "2") (pinfunction "2_2") (pintype "passive"))
      (node (ref "R48") (pin "1") (pinfunction "1_1") (pintype "passive"))
      (node (ref "R58") (pin "2") (pinfunction "2_2") (pintype "passive"))
      (node (ref "U$1") (pin "AA2") (pinfunction "1_AA2") (pintype "bidirectional"))
    )
    (net (code "2") (name "-15V") (class "Default")
      (node (ref "R1") (pin "1") (pinfunction "1_1") (pintype "passive"))
      (node (ref "R10") (pin "1") (pinfunction "1_1") (pintype "passive"))
      (node (ref "R11") (pin "1") (pinfunction "1_1") (pintype "passive"))
      (node (ref "R12") (pin "1") (pinfunction "1_1") (pintype "passive"))
      (node (ref "R13") (pin "1") (pinfunction "1_1") (pintype "passive"))
      (node (ref "R14") (pin "1") (pinfunction "1_1") (pintype "passive"))
      (node (ref "R15") (pin "1") (pinfunction "1_1") (pintype "passive"))
      (node (ref "R16") (pin "1") (pinfunction "1_1") (pintype "passive"))
      (node (ref "R18") (pin "1") (pinfunction "1_1") (pintype "passive"))
      (node (ref "R2") (pin "1") (pinfunction "1_1") (pintype "passive"))
      (node (ref "R20") (pin "1") (pinfunction "1_1") (pintype "passive"))
      (node (ref "R21") (pin "1") (pinfunction "1_1") (pintype "passive"))
      (node (ref "R23") (pin "1") (pinfunction "1_1") (pintype "passive"))
      (node (ref "R24") (pin "1") (pinfunction "1_1") (pintype "passive"))
      (node (ref "R26") (pin "1") (pinfunction "1_1") (pintype "passive"))
      (node (ref "R27") (pin "1") (pinfunction "1_1") (pintype "passive"))
      (node (ref "R29") (pin "1") (pinfunction "1_1") (pintype "passive"))
      (node (ref "R3") (pin "1") (pinfunction "1_1") (pintype "passive"))
      (node (ref "R30") (pin "1") (pinfunction "1_1") (pintype "passive"))
      (node (ref "R31") (pin "1") (pinfunction "1_1") (pintype "passive"))
      (node (ref "R32") (pin "1") (pinfunction "1_1") (pintype "passive"))
      (node (ref "R33") (pin "1") (pinfunction "1_1") (pintype "passive"))
      (node (ref "R35") (pin "1") (pinfunction "1_1") (pintype "passive"))
      (node (ref "R37") (pin "1") (pinfunction "1_1") (pintype "passive"))
      (node (ref "R38") (pin "1") (pinfunction "1_1") (pintype "passive"))
      (node (ref "R39") (pin "1") (pinfunction "1_1") (pintype "passive"))
      (node (ref "R4") (pin "1") (pinfunction "1_1") (pintype "passive"))
      (node (ref "R40") (pin "1") (pinfunction "1_1") (pintype "passive"))
      (node (ref "R41") (pin "1") (pinfunction "1_1") (pintype "passive"))
      (node (ref "R42") (pin "1") (pinfunction "1_1") (pintype "passive"))
      (node (ref "R43") (pin "1") (pinfunction "1_1") (pintype "passive"))
      (node (ref "R44") (pin "1") (pinfunction "1_1") (pintype "passive"))
      (node (ref "R45") (pin "1") (pinfunction "1_1") (pintype "passive"))
      (node (ref "R46") (pin "1") (pinfunction "1_1") (pintype "passive"))
      (node (ref "R47") (pin "1") (pinfunction "1_1") (pintype "passive"))
      (node (ref "R49") (pin "1") (pinfunction "1_1") (pintype "passive"))
      (node (ref "R5") (pin "1") (pinfunction "1_1") (pintype "passive"))
      (node (ref "R50") (pin "1") (pinfunction "1_1") (pintype "passive"))
      (node (ref "R51") (pin "1") (pinfunction "1_1") (pintype "passive"))
      (node (ref "R52") (pin "1") (pinfunction "1_1") (pintype "passive"))
      (node (ref "R53") (pin "1") (pinfunction "1_1") (pintype "passive"))
      (node (ref "R54") (pin "1") (pinfunction "1_1") (pintype "passive"))
      (node (ref "R55") (pin "1") (pinfunction "1_1") (pintype "passive"))
      (node (ref "R56") (pin "1") (pinfunction "1_1") (pintype "passive"))
      (node (ref "R57") (pin "1") (pinfunction "1_1") (pintype "passive"))
      (node (ref "R59") (pin "1") (pinfunction "1_1") (pintype "passive"))
      (node (ref "R6") (pin "1") (pinfunction "1_1") (pintype "passive"))
      (node (ref "R60") (pin "1") (pinfunction "1_1") (pintype "passive"))
      (node (ref "R61") (pin "1") (pinfunction "1_1") (pintype "passive"))
      (node (ref "R62") (pin "1") (pinfunction "1_1") (pintype "passive"))
      (node (ref "R63") (pin "1") (pinfunction "1_1") (pintype "passive"))
      (node (ref "R64") (pin "1") (pinfunction "1_1") (pintype "passive"))
      (node (ref "R65") (pin "1") (pinfunction "1_1") (pintype "passive"))
      (node (ref "R67") (pin "1") (pinfunction "1_1") (pintype "passive"))
      (node (ref "R7") (pin "1") (pinfunction "1_1") (pintype "passive"))
      (node (ref "R71") (pin "1") (pinfunction "1_1") (pintype "passive"))
      (node (ref "R73") (pin "1") (pinfunction "1_1") (pintype "passive"))
      (node (ref "R75") (pin "1") (pinfunction "1_1") (pintype "passive"))
      (node (ref "R8") (pin "1") (pinfunction "1_1") (pintype "passive"))
      (node (ref "R9") (pin "1") (pinfunction "1_1") (pintype "passive"))
      (node (ref "U$1") (pin "AB2") (pinfunction "1_AB2") (pintype "bidirectional"))
    )
    (net (code "3") (name "/-0.7V") (class "Default")
      (node (ref "D1") (pin "C") (pinfunction "C_C") (pintype "passive"))
      (node (ref "D103") (pin "C") (pinfunction "C_C") (pintype "passive"))
      (node (ref "D104") (pin "C") (pinfunction "C_C") (pintype "passive"))
      (node (ref "D107") (pin "C") (pinfunction "C_C") (pintype "passive"))
      (node (ref "D109") (pin "C") (pinfunction "C_C") (pintype "passive"))
      (node (ref "D11") (pin "C") (pinfunction "C_C") (pintype "passive"))
      (node (ref "D112") (pin "A") (pinfunction "A_A") (pintype "passive"))
      (node (ref "D113") (pin "C") (pinfunction "C_C") (pintype "passive"))
      (node (ref "D115") (pin "C") (pinfunction "C_C") (pintype "passive"))
      (node (ref "D121") (pin "C") (pinfunction "C_C") (pintype "passive"))
      (node (ref "D124") (pin "C") (pinfunction "C_C") (pintype "passive"))
      (node (ref "D128") (pin "C") (pinfunction "C_C") (pintype "passive"))
      (node (ref "D130") (pin "C") (pinfunction "C_C") (pintype "passive"))
      (node (ref "D133") (pin "C") (pinfunction "C_C") (pintype "passive"))
      (node (ref "D22") (pin "C") (pinfunction "C_C") (pintype "passive"))
      (node (ref "D24") (pin "C") (pinfunction "C_C") (pintype "passive"))
      (node (ref "D25") (pin "C") (pinfunction "C_C") (pintype "passive"))
      (node (ref "D60") (pin "C") (pinfunction "C_C") (pintype "passive"))
      (node (ref "D75") (pin "C") (pinfunction "C_C") (pintype "passive"))
      (node (ref "D79") (pin "C") (pinfunction "C_C") (pintype "passive"))
      (node (ref "D81") (pin "C") (pinfunction "C_C") (pintype "passive"))
      (node (ref "D84") (pin "C") (pinfunction "C_C") (pintype "passive"))
      (node (ref "D90") (pin "C") (pinfunction "C_C") (pintype "passive"))
      (node (ref "D92") (pin "C") (pinfunction "C_C") (pintype "passive"))
      (node (ref "D95") (pin "C") (pinfunction "C_C") (pintype "passive"))
      (node (ref "D97") (pin "C") (pinfunction "C_C") (pintype "passive"))
    )
    (net (code "4") (name "/-3V") (class "Default")
      (node (ref "C18") (pin "2") (pinfunction "2_2") (pintype "passive"))
      (node (ref "D110") (pin "C") (pinfunction "C_C") (pintype "passive"))
      (node (ref "D122") (pin "A") (pinfunction "A_A") (pintype "passive"))
      (node (ref "D127") (pin "A") (pinfunction "A_A") (pintype "passive"))
      (node (ref "D134") (pin "A") (pinfunction "A_A") (pintype "passive"))
      (node (ref "D135") (pin "A") (pinfunction "A_A") (pintype "passive"))
      (node (ref "D136") (pin "A") (pinfunction "A_A") (pintype "passive"))
      (node (ref "D137") (pin "A") (pinfunction "A_A") (pintype "passive"))
      (node (ref "D138") (pin "A") (pinfunction "A_A") (pintype "passive"))
      (node (ref "D38") (pin "A") (pinfunction "A_A") (pintype "passive"))
      (node (ref "D48") (pin "A") (pinfunction "A_A") (pintype "passive"))
      (node (ref "D50") (pin "A") (pinfunction "A_A") (pintype "passive"))
      (node (ref "D52") (pin "A") (pinfunction "A_A") (pintype "passive"))
      (node (ref "D57") (pin "A") (pinfunction "A_A") (pintype "passive"))
      (node (ref "D61") (pin "A") (pinfunction "A_A") (pintype "passive"))
      (node (ref "D74") (pin "A") (pinfunction "A_A") (pintype "passive"))
      (node (ref "R54") (pin "2") (pinfunction "2_2") (pintype "passive"))
    )
    (net (code "5") (name "/AC") (class "Default")
      (node (ref "D106") (pin "A") (pinfunction "A_A") (pintype "passive"))
      (node (ref "D107") (pin "A") (pinfunction "A_A") (pintype "passive"))
      (node (ref "U$1") (pin "BN2") (pinfunction "1_BN2") (pintype "bidirectional"))
    )
    (net (code "6") (name "/AC2MB") (class "Default")
      (node (ref "D96") (pin "A") (pinfunction "A_A") (pintype "passive"))
      (node (ref "D97") (pin "A") (pinfunction "A_A") (pintype "passive"))
      (node (ref "U$1") (pin "BT2") (pinfunction "1_BT2") (pintype "bidirectional"))
    )
    (net (code "7") (name "/CLEAR_MA") (class "Default")
      (node (ref "D41") (pin "A") (pinfunction "A_A") (pintype "passive"))
      (node (ref "U$1") (pin "AJ2") (pinfunction "1_AJ2") (pintype "bidirectional"))
    )
    (net (code "8") (name "/CLEAR_MA2") (class "Default")
      (node (ref "D40") (pin "A") (pinfunction "A_A") (pintype "passive"))
      (node (ref "U$1") (pin "AL2") (pinfunction "1_AL2") (pintype "bidirectional"))
    )
    (net (code "9") (name "/CLEAR_MB") (class "Default")
      (node (ref "D43") (pin "A") (pinfunction "A_A") (pintype "passive"))
      (node (ref "U$1") (pin "AU2") (pinfunction "1_AU2") (pintype "bidirectional"))
    )
    (net (code "10") (name "/CLEAR_PC") (class "Default")
      (node (ref "D30") (pin "A") (pinfunction "A_A") (pintype "passive"))
      (node (ref "U$1") (pin "AV2") (pinfunction "1_AV2") (pintype "bidirectional"))
    )
    (net (code "11") (name "/COMP_PC_PULSE") (class "Default")
      (node (ref "D15") (pin "A") (pinfunction "A_A") (pintype "passive"))
      (node (ref "D60") (pin "A") (pinfunction "A_A") (pintype "passive"))
      (node (ref "D63") (pin "A") (pinfunction "A_A") (pintype "passive"))
      (node (ref "U$1") (pin "BD2") (pinfunction "1_BD2") (pintype "bidirectional"))
    )
    (net (code "12") (name "/COUNT_MB") (class "Default")
      (node (ref "D26") (pin "A") (pinfunction "A_A") (pintype "passive"))
      (node (ref "D80") (pin "A") (pinfunction "A_A") (pintype "passive"))
      (node (ref "D81") (pin "A") (pinfunction "A_A") (pintype "passive"))
      (node (ref "U$1") (pin "BJ2") (pinfunction "1_BJ2") (pintype "bidirectional"))
    )
    (net (code "13") (name "/CPC_LVL") (class "Default")
      (node (ref "D23") (pin "A") (pinfunction "A_A") (pintype "passive"))
      (node (ref "D73") (pin "A") (pinfunction "A_A") (pintype "passive"))
      (node (ref "D75") (pin "A") (pinfunction "A_A") (pintype "passive"))
      (node (ref "U$1") (pin "BE2") (pinfunction "1_BE2") (pintype "bidirectional"))
    )
    (net (code "14") (name "/DADDR2MA") (class "Default")
      (node (ref "D100") (pin "A") (pinfunction "A_A") (pintype "passive"))
      (node (ref "D103") (pin "A") (pinfunction "A_A") (pintype "passive"))
      (node (ref "D2") (pin "A") (pinfunction "A_A") (pintype "passive"))
      (node (ref "U$1") (pin "AP2") (pinfunction "1_AP2") (pintype "bidirectional"))
    )
    (net (code "15") (name "/DATA") (class "Default")
      (node (ref "D132") (pin "A") (pinfunction "A_A") (pintype "passive"))
      (node (ref "D133") (pin "A") (pinfunction "A_A") (pintype "passive"))
      (node (ref "D138") (pin "C") (pinfunction "C_C") (pintype "passive"))
      (node (ref "R63") (pin "2") (pinfunction "2_2") (pintype "passive"))
      (node (ref "U$1") (pin "BM2") (pinfunction "1_BM2") (pintype "bidirectional"))
    )
    (net (code "16") (name "/DATA2MB") (class "Default")
      (node (ref "D129") (pin "A") (pinfunction "A_A") (pintype "passive"))
      (node (ref "D130") (pin "A") (pinfunction "A_A") (pintype "passive"))
      (node (ref "U$1") (pin "BS2") (pinfunction "1_BS2") (pintype "bidirectional"))
    )
    (net (code "17") (name "/MA=0") (class "Default")
      (node (ref "C24") (pin "2") (pinfunction "2_2") (pintype "passive"))
      (node (ref "D57") (pin "C") (pinfunction "C_C") (pintype "passive"))
      (node (ref "D58") (pin "A") (pinfunction "A_A") (pintype "passive"))
      (node (ref "Q4") (pin "3") (pinfunction "C_3") (pintype "passive"))
      (node (ref "R30") (pin "2") (pinfunction "2_2") (pintype "passive"))
      (node (ref "R72") (pin "2") (pinfunction "2_2") (pintype "passive"))
    )
    (net (code "18") (name "/MA=1") (class "Default")
      (node (ref "C23") (pin "2") (pinfunction "2_2") (pintype "passive"))
      (node (ref "D48") (pin "C") (pinfunction "C_C") (pintype "passive"))
      (node (ref "D49") (pin "A") (pinfunction "A_A") (pintype "passive"))
      (node (ref "Q6") (pin "3") (pinfunction "C_3") (pintype "passive"))
      (node (ref "R26") (pin "2") (pinfunction "2_2") (pintype "passive"))
      (node (ref "R66") (pin "2") (pinfunction "2_2") (pintype "passive"))
    )
    (net (code "19") (name "/MAOUT0") (class "Default")
      (node (ref "D127") (pin "C") (pinfunction "C_C") (pintype "passive"))
      (node (ref "Q10") (pin "3") (pinfunction "C_3") (pintype "passive"))
      (node (ref "R65") (pin "2") (pinfunction "2_2") (pintype "passive"))
      (node (ref "U$1") (pin "AE2") (pinfunction "1_AE2") (pintype "bidirectional"))
    )
    (net (code "20") (name "/MAOUT1") (class "Default")
      (node (ref "D134") (pin "C") (pinfunction "C_C") (pintype "passive"))
      (node (ref "Q11") (pin "3") (pinfunction "C_3") (pintype "passive"))
      (node (ref "R71") (pin "2") (pinfunction "2_2") (pintype "passive"))
      (node (ref "U$1") (pin "AH2") (pinfunction "1_AH2") (pintype "bidirectional"))
    )
    (net (code "21") (name "/MB2MA") (class "Default")
      (node (ref "D14") (pin "A") (pinfunction "A_A") (pintype "passive"))
      (node (ref "D89") (pin "A") (pinfunction "A_A") (pintype "passive"))
      (node (ref "D90") (pin "A") (pinfunction "A_A") (pintype "passive"))
      (node (ref "U$1") (pin "AN2") (pinfunction "1_AN2") (pintype "bidirectional"))
    )
    (net (code "22") (name "/MB2PC") (class "Default")
      (node (ref "D3") (pin "A") (pinfunction "A_A") (pintype "passive"))
      (node (ref "D77") (pin "A") (pinfunction "A_A") (pintype "passive"))
      (node (ref "D84") (pin "A") (pinfunction "A_A") (pintype "passive"))
      (node (ref "U$1") (pin "BA2") (pinfunction "1_BA2") (pintype "bidirectional"))
    )
    (net (code "23") (name "/MB=0") (class "Default")
      (node (ref "C21") (pin "2") (pinfunction "2_2") (pintype "passive"))
      (node (ref "D61") (pin "C") (pinfunction "C_C") (pintype "passive"))
      (node (ref "D62") (pin "A") (pinfunction "A_A") (pintype "passive"))
      (node (ref "D78") (pin "A") (pinfunction "A_A") (pintype "passive"))
      (node (ref "D87") (pin "A") (pinfunction "A_A") (pintype "passive"))
      (node (ref "D95") (pin "A") (pinfunction "A_A") (pintype "passive"))
      (node (ref "D98") (pin "A") (pinfunction "A_A") (pintype "passive"))
      (node (ref "Q5") (pin "3") (pinfunction "C_3") (pintype "passive"))
      (node (ref "R31") (pin "2") (pinfunction "2_2") (pintype "passive"))
      (node (ref "R70") (pin "2") (pinfunction "2_2") (pintype "passive"))
    )
    (net (code "24") (name "/MB=1") (class "Default")
      (node (ref "C22") (pin "2") (pinfunction "2_2") (pintype "passive"))
      (node (ref "D21") (pin "A") (pinfunction "A_A") (pintype "passive"))
      (node (ref "D22") (pin "A") (pinfunction "A_A") (pintype "passive"))
      (node (ref "D27") (pin "A") (pinfunction "A_A") (pintype "passive"))
      (node (ref "D52") (pin "C") (pinfunction "C_C") (pintype "passive"))
      (node (ref "D53") (pin "A") (pinfunction "A_A") (pintype "passive"))
      (node (ref "D9") (pin "A") (pinfunction "A_A") (pintype "passive"))
      (node (ref "Q7") (pin "3") (pinfunction "C_3") (pintype "passive"))
      (node (ref "R29") (pin "2") (pinfunction "2_2") (pintype "passive"))
      (node (ref "R74") (pin "2") (pinfunction "2_2") (pintype "passive"))
    )
    (net (code "25") (name "/MBCARRYENA") (class "Default")
      (node (ref "D25") (pin "A") (pinfunction "A_A") (pintype "passive"))
      (node (ref "D36") (pin "A") (pinfunction "A_A") (pintype "passive"))
      (node (ref "D88") (pin "A") (pinfunction "A_A") (pintype "passive"))
      (node (ref "U$1") (pin "BH2") (pinfunction "1_BH2") (pintype "bidirectional"))
    )
    (net (code "26") (name "/MBOUT0") (class "Default")
      (node (ref "D136") (pin "C") (pinfunction "C_C") (pintype "passive"))
      (node (ref "Q13") (pin "3") (pinfunction "C_3") (pintype "passive"))
      (node (ref "R75") (pin "2") (pinfunction "2_2") (pintype "passive"))
      (node (ref "U$1") (pin "AD2") (pinfunction "1_AD2") (pintype "bidirectional"))
    )
    (net (code "27") (name "/MBOUT1") (class "Default")
      (node (ref "D135") (pin "C") (pinfunction "C_C") (pintype "passive"))
      (node (ref "Q12") (pin "3") (pinfunction "C_3") (pintype "passive"))
      (node (ref "R73") (pin "2") (pinfunction "2_2") (pintype "passive"))
      (node (ref "U$1") (pin "AF2") (pinfunction "1_AF2") (pintype "bidirectional"))
    )
    (net (code "28") (name "/PC2MA") (class "Default")
      (node (ref "D29") (pin "A") (pinfunction "A_A") (pintype "passive"))
      (node (ref "D76") (pin "A") (pinfunction "A_A") (pintype "passive"))
      (node (ref "D79") (pin "A") (pinfunction "A_A") (pintype "passive"))
      (node (ref "U$1") (pin "AM2") (pinfunction "1_AM2") (pintype "bidirectional"))
    )
    (net (code "29") (name "/PC2MB") (class "Default")
      (node (ref "D114") (pin "A") (pinfunction "A_A") (pintype "passive"))
      (node (ref "D115") (pin "A") (pinfunction "A_A") (pintype "passive"))
      (node (ref "D12") (pin "A") (pinfunction "A_A") (pintype "passive"))
      (node (ref "U$1") (pin "BV2") (pinfunction "1_BV2") (pintype "bidirectional"))
    )
    (net (code "30") (name "/PC=0") (class "Default")
      (node (ref "D120") (pin "A") (pinfunction "A_A") (pintype "passive"))
      (node (ref "D121") (pin "A") (pinfunction "A_A") (pintype "passive"))
      (node (ref "D50") (pin "C") (pinfunction "C_C") (pintype "passive"))
      (node (ref "D51") (pin "A") (pinfunction "A_A") (pintype "passive"))
      (node (ref "D59") (pin "A") (pinfunction "A_A") (pintype "passive"))
      (node (ref "D86") (pin "A") (pinfunction "A_A") (pintype "passive"))
      (node (ref "Q2") (pin "3") (pinfunction "C_3") (pintype "passive"))
      (node (ref "R23") (pin "2") (pinfunction "2_2") (pintype "passive"))
      (node (ref "U$1") (pin "BL2") (pinfunction "1_BL2") (pintype "bidirectional"))
    )
    (net (code "31") (name "/PC=1") (class "Default")
      (node (ref "D13") (pin "A") (pinfunction "A_A") (pintype "passive"))
      (node (ref "D18") (pin "A") (pinfunction "A_A") (pintype "passive"))
      (node (ref "D24") (pin "A") (pinfunction "A_A") (pintype "passive"))
      (node (ref "D37") (pin "A") (pinfunction "A_A") (pintype "passive"))
      (node (ref "D38") (pin "C") (pinfunction "C_C") (pintype "passive"))
      (node (ref "D39") (pin "A") (pinfunction "A_A") (pintype "passive"))
      (node (ref "Q3") (pin "3") (pinfunction "C_3") (pintype "passive"))
      (node (ref "R20") (pin "2") (pinfunction "2_2") (pintype "passive"))
      (node (ref "U$1") (pin "BK2") (pinfunction "1_BK2") (pintype "bidirectional"))
    )
    (net (code "32") (name "/SET_MA") (class "Default")
      (node (ref "D69") (pin "A") (pinfunction "A_A") (pintype "passive"))
      (node (ref "U$1") (pin "AK2") (pinfunction "1_AK2") (pintype "bidirectional"))
    )
    (net (code "33") (name "/SET_MB") (class "Default")
      (node (ref "D70") (pin "A") (pinfunction "A_A") (pintype "passive"))
      (node (ref "D74") (pin "C") (pinfunction "C_C") (pintype "passive"))
      (node (ref "R38") (pin "2") (pinfunction "2_2") (pintype "passive"))
      (node (ref "U$1") (pin "AT2") (pinfunction "1_AT2") (pintype "bidirectional"))
    )
    (net (code "34") (name "/SHIFT") (class "Default")
      (node (ref "D123") (pin "A") (pinfunction "A_A") (pintype "passive"))
      (node (ref "D124") (pin "A") (pinfunction "A_A") (pintype "passive"))
      (node (ref "D4") (pin "A") (pinfunction "A_A") (pintype "passive"))
      (node (ref "U$1") (pin "BU2") (pinfunction "1_BU2") (pintype "bidirectional"))
    )
    (net (code "35") (name "/SR") (class "Default")
      (node (ref "D101") (pin "A") (pinfunction "A_A") (pintype "passive"))
      (node (ref "D104") (pin "A") (pinfunction "A_A") (pintype "passive"))
      (node (ref "U$1") (pin "BF2") (pinfunction "1_BF2") (pintype "bidirectional"))
    )
    (net (code "36") (name "/SR2PC") (class "Default")
      (node (ref "D91") (pin "A") (pinfunction "A_A") (pintype "passive"))
      (node (ref "D92") (pin "A") (pinfunction "A_A") (pintype "passive"))
      (node (ref "U$1") (pin "BB2") (pinfunction "1_BB2") (pintype "bidirectional"))
    )
    (net (code "37") (name "GND") (class "Default")
      (node (ref "C18") (pin "1") (pinfunction "1_1") (pintype "passive"))
      (node (ref "D113") (pin "A") (pinfunction "A_A") (pintype "passive"))
      (node (ref "Q10") (pin "1") (pinfunction "E_1") (pintype "passive"))
      (node (ref "Q11") (pin "1") (pinfunction "E_1") (pintype "passive"))
      (node (ref "Q12") (pin "1") (pinfunction "E_1") (pintype "passive"))
      (node (ref "Q13") (pin "1") (pinfunction "E_1") (pintype "passive"))
      (node (ref "Q2") (pin "1") (pinfunction "E_1") (pintype "passive"))
      (node (ref "Q3") (pin "1") (pinfunction "E_1") (pintype "passive"))
      (node (ref "Q4") (pin "1") (pinfunction "E_1") (pintype "passive"))
      (node (ref "Q5") (pin "1") (pinfunction "E_1") (pintype "passive"))
      (node (ref "Q6") (pin "1") (pinfunction "E_1") (pintype "passive"))
      (node (ref "Q7") (pin "1") (pinfunction "E_1") (pintype "passive"))
      (node (ref "Q9") (pin "1") (pinfunction "E_1") (pintype "passive"))
      (node (ref "U$1") (pin "AC2") (pinfunction "1_AC2") (pintype "bidirectional"))
      (node (ref "U$1") (pin "BC2") (pinfunction "1_BC2") (pintype "bidirectional"))
    )
    (net (code "38") (name "Net-(C1-Pad1)") (class "Default")
      (node (ref "C1") (pin "1") (pinfunction "1_1") (pintype "passive"))
      (node (ref "D2") (pin "C") (pinfunction "C_C") (pintype "passive"))
      (node (ref "R1") (pin "2") (pinfunction "2_2") (pintype "passive"))
    )
    (net (code "39") (name "Net-(C1-Pad2)") (class "Default")
      (node (ref "C1") (pin "2") (pinfunction "2_2") (pintype "passive"))
      (node (ref "D5") (pin "A") (pinfunction "A_A") (pintype "passive"))
      (node (ref "D8") (pin "C") (pinfunction "C_C") (pintype "passive"))
      (node (ref "R4") (pin "2") (pinfunction "2_2") (pintype "passive"))
    )
    (net (code "40") (name "Net-(C2-Pad1)") (class "Default")
      (node (ref "C2") (pin "1") (pinfunction "1_1") (pintype "passive"))
      (node (ref "D3") (pin "C") (pinfunction "C_C") (pintype "passive"))
      (node (ref "R2") (pin "2") (pinfunction "2_2") (pintype "passive"))
    )
    (net (code "41") (name "Net-(C2-Pad2)") (class "Default")
      (node (ref "C2") (pin "2") (pinfunction "2_2") (pintype "passive"))
      (node (ref "D6") (pin "A") (pinfunction "A_A") (pintype "passive"))
      (node (ref "D9") (pin "C") (pinfunction "C_C") (pintype "passive"))
      (node (ref "R5") (pin "2") (pinfunction "2_2") (pintype "passive"))
    )
    (net (code "42") (name "Net-(C3-Pad1)") (class "Default")
      (node (ref "C3") (pin "1") (pinfunction "1_1") (pintype "passive"))
      (node (ref "D4") (pin "C") (pinfunction "C_C") (pintype "passive"))
      (node (ref "R3") (pin "2") (pinfunction "2_2") (pintype "passive"))
    )
    (net (code "43") (name "Net-(C3-Pad2)") (class "Default")
      (node (ref "C3") (pin "2") (pinfunction "2_2") (pintype "passive"))
      (node (ref "D10") (pin "C") (pinfunction "C_C") (pintype "passive"))
      (node (ref "D7") (pin "A") (pinfunction "A_A") (pintype "passive"))
      (node (ref "R6") (pin "2") (pinfunction "2_2") (pintype "passive"))
    )
    (net (code "44") (name "Net-(C4-Pad1)") (class "Default")
      (node (ref "C4") (pin "1") (pinfunction "1_1") (pintype "passive"))
      (node (ref "D12") (pin "C") (pinfunction "C_C") (pintype "passive"))
      (node (ref "R7") (pin "2") (pinfunction "2_2") (pintype "passive"))
    )
    (net (code "45") (name "Net-(C4-Pad2)") (class "Default")
      (node (ref "C4") (pin "2") (pinfunction "2_2") (pintype "passive"))
      (node (ref "D16") (pin "A") (pinfunction "A_A") (pintype "passive"))
      (node (ref "D18") (pin "C") (pinfunction "C_C") (pintype "passive"))
      (node (ref "R10") (pin "2") (pinfunction "2_2") (pintype "passive"))
    )
    (net (code "46") (name "Net-(C5-Pad1)") (class "Default")
      (node (ref "C5") (pin "1") (pinfunction "1_1") (pintype "passive"))
      (node (ref "D14") (pin "C") (pinfunction "C_C") (pintype "passive"))
      (node (ref "R8") (pin "2") (pinfunction "2_2") (pintype "passive"))
    )
    (net (code "47") (name "Net-(C5-Pad2)") (class "Default")
      (node (ref "C5") (pin "2") (pinfunction "2_2") (pintype "passive"))
      (node (ref "D19") (pin "A") (pinfunction "A_A") (pintype "passive"))
      (node (ref "D21") (pin "C") (pinfunction "C_C") (pintype "passive"))
      (node (ref "R11") (pin "2") (pinfunction "2_2") (pintype "passive"))
    )
    (net (code "48") (name "Net-(C6-Pad1)") (class "Default")
      (node (ref "C6") (pin "1") (pinfunction "1_1") (pintype "passive"))
      (node (ref "D13") (pin "C") (pinfunction "C_C") (pintype "passive"))
      (node (ref "D15") (pin "C") (pinfunction "C_C") (pintype "passive"))
      (node (ref "D17") (pin "A") (pinfunction "A_A") (pintype "passive"))
      (node (ref "R9") (pin "2") (pinfunction "2_2") (pintype "passive"))
    )
    (net (code "49") (name "Net-(C6-Pad2)") (class "Default")
      (node (ref "C6") (pin "2") (pinfunction "2_2") (pintype "passive"))
      (node (ref "D17") (pin "C") (pinfunction "C_C") (pintype "passive"))
      (node (ref "D20") (pin "A") (pinfunction "A_A") (pintype "passive"))
      (node (ref "D23") (pin "C") (pinfunction "C_C") (pintype "passive"))
      (node (ref "R12") (pin "2") (pinfunction "2_2") (pintype "passive"))
    )
    (net (code "50") (name "Net-(C7-Pad1)") (class "Default")
      (node (ref "C7") (pin "1") (pinfunction "1_1") (pintype "passive"))
      (node (ref "D26") (pin "C") (pinfunction "C_C") (pintype "passive"))
      (node (ref "D27") (pin "C") (pinfunction "C_C") (pintype "passive"))
      (node (ref "D28") (pin "A") (pinfunction "A_A") (pintype "passive"))
      (node (ref "R13") (pin "2") (pinfunction "2_2") (pintype "passive"))
    )
    (net (code "51") (name "Net-(C8-Pad1)") (class "Default")
      (node (ref "C8") (pin "1") (pinfunction "1_1") (pintype "passive"))
      (node (ref "D29") (pin "C") (pinfunction "C_C") (pintype "passive"))
      (node (ref "R14") (pin "2") (pinfunction "2_2") (pintype "passive"))
    )
    (net (code "52") (name "Net-(C8-Pad2)") (class "Default")
      (node (ref "C8") (pin "2") (pinfunction "2_2") (pintype "passive"))
      (node (ref "D33") (pin "A") (pinfunction "A_A") (pintype "passive"))
      (node (ref "D37") (pin "C") (pinfunction "C_C") (pintype "passive"))
      (node (ref "R18") (pin "2") (pinfunction "2_2") (pintype "passive"))
    )
    (net (code "53") (name "Net-(C9-Pad1)") (class "Default")
      (node (ref "C9") (pin "1") (pinfunction "1_1") (pintype "passive"))
      (node (ref "D59") (pin "C") (pinfunction "C_C") (pintype "passive"))
      (node (ref "D63") (pin "C") (pinfunction "C_C") (pintype "passive"))
      (node (ref "D66") (pin "A") (pinfunction "A_A") (pintype "passive"))
      (node (ref "R32") (pin "2") (pinfunction "2_2") (pintype "passive"))
    )
    (net (code "54") (name "Net-(C9-Pad2)") (class "Default")
      (node (ref "C9") (pin "2") (pinfunction "2_2") (pintype "passive"))
      (node (ref "D66") (pin "C") (pinfunction "C_C") (pintype "passive"))
      (node (ref "D72") (pin "A") (pinfunction "A_A") (pintype "passive"))
      (node (ref "D73") (pin "C") (pinfunction "C_C") (pintype "passive"))
      (node (ref "R37") (pin "2") (pinfunction "2_2") (pintype "passive"))
    )
    (net (code "55") (name "Net-(C10-Pad1)") (class "Default")
      (node (ref "C10") (pin "1") (pinfunction "1_1") (pintype "passive"))
      (node (ref "D76") (pin "C") (pinfunction "C_C") (pintype "passive"))
      (node (ref "R39") (pin "2") (pinfunction "2_2") (pintype "passive"))
    )
    (net (code "56") (name "Net-(C10-Pad2)") (class "Default")
      (node (ref "C10") (pin "2") (pinfunction "2_2") (pintype "passive"))
      (node (ref "D82") (pin "A") (pinfunction "A_A") (pintype "passive"))
      (node (ref "D86") (pin "C") (pinfunction "C_C") (pintype "passive"))
      (node (ref "R42") (pin "2") (pinfunction "2_2") (pintype "passive"))
    )
    (net (code "57") (name "Net-(C11-Pad1)") (class "Default")
      (node (ref "C11") (pin "1") (pinfunction "1_1") (pintype "passive"))
      (node (ref "D77") (pin "C") (pinfunction "C_C") (pintype "passive"))
      (node (ref "R40") (pin "2") (pinfunction "2_2") (pintype "passive"))
    )
    (net (code "58") (name "Net-(C11-Pad2)") (class "Default")
      (node (ref "C11") (pin "2") (pinfunction "2_2") (pintype "passive"))
      (node (ref "D83") (pin "A") (pinfunction "A_A") (pintype "passive"))
      (node (ref "D87") (pin "C") (pinfunction "C_C") (pintype "passive"))
      (node (ref "R43") (pin "2") (pinfunction "2_2") (pintype "passive"))
    )
    (net (code "59") (name "Net-(C12-Pad1)") (class "Default")
      (node (ref "C12") (pin "1") (pinfunction "1_1") (pintype "passive"))
      (node (ref "D78") (pin "C") (pinfunction "C_C") (pintype "passive"))
      (node (ref "D80") (pin "C") (pinfunction "C_C") (pintype "passive"))
      (node (ref "D85") (pin "A") (pinfunction "A_A") (pintype "passive"))
      (node (ref "R41") (pin "2") (pinfunction "2_2") (pintype "passive"))
    )
    (net (code "60") (name "Net-(C13-Pad1)") (class "Default")
      (node (ref "C13") (pin "1") (pinfunction "1_1") (pintype "passive"))
      (node (ref "D89") (pin "C") (pinfunction "C_C") (pintype "passive"))
      (node (ref "R45") (pin "2") (pinfunction "2_2") (pintype "passive"))
    )
    (net (code "61") (name "Net-(C13-Pad2)") (class "Default")
      (node (ref "C13") (pin "2") (pinfunction "2_2") (pintype "passive"))
      (node (ref "D94") (pin "A") (pinfunction "A_A") (pintype "passive"))
      (node (ref "D98") (pin "C") (pinfunction "C_C") (pintype "passive"))
      (node (ref "R46") (pin "2") (pinfunction "2_2") (pintype "passive"))
    )
    (net (code "62") (name "Net-(C14-Pad1)") (class "Default")
      (node (ref "C14") (pin "1") (pinfunction "1_1") (pintype "passive"))
      (node (ref "D91") (pin "C") (pinfunction "C_C") (pintype "passive"))
      (node (ref "R47") (pin "2") (pinfunction "2_2") (pintype "passive"))
    )
    (net (code "63") (name "Net-(C14-Pad2)") (class "Default")
      (node (ref "C14") (pin "2") (pinfunction "2_2") (pintype "passive"))
      (node (ref "D101") (pin "C") (pinfunction "C_C") (pintype "passive"))
      (node (ref "D99") (pin "A") (pinfunction "A_A") (pintype "passive"))
      (node (ref "R50") (pin "2") (pinfunction "2_2") (pintype "passive"))
    )
    (net (code "64") (name "Net-(C15-Pad1)") (class "Default")
      (node (ref "C15") (pin "1") (pinfunction "1_1") (pintype "passive"))
      (node (ref "D96") (pin "C") (pinfunction "C_C") (pintype "passive"))
      (node (ref "R49") (pin "2") (pinfunction "2_2") (pintype "passive"))
    )
    (net (code "65") (name "Net-(C15-Pad2)") (class "Default")
      (node (ref "C15") (pin "2") (pinfunction "2_2") (pintype "passive"))
      (node (ref "D102") (pin "A") (pinfunction "A_A") (pintype "passive"))
      (node (ref "D106") (pin "C") (pinfunction "C_C") (pintype "passive"))
      (node (ref "R52") (pin "2") (pinfunction "2_2") (pintype "passive"))
    )
    (net (code "66") (name "Net-(C16-Pad1)") (class "Default")
      (node (ref "C16") (pin "1") (pinfunction "1_1") (pintype "passive"))
      (node (ref "D100") (pin "C") (pinfunction "C_C") (pintype "passive"))
      (node (ref "R51") (pin "2") (pinfunction "2_2") (pintype "passive"))
    )
    (net (code "67") (name "Net-(C16-Pad2)") (class "Default")
      (node (ref "C16") (pin "2") (pinfunction "2_2") (pintype "passive"))
      (node (ref "D105") (pin "A") (pinfunction "A_A") (pintype "passive"))
      (node (ref "D108") (pin "C") (pinfunction "C_C") (pintype "passive"))
      (node (ref "R53") (pin "2") (pinfunction "2_2") (pintype "passive"))
    )
    (net (code "68") (name "Net-(C17-Pad1)") (class "Default")
      (node (ref "C17") (pin "1") (pinfunction "1_1") (pintype "passive"))
      (node (ref "D114") (pin "C") (pinfunction "C_C") (pintype "passive"))
      (node (ref "R55") (pin "2") (pinfunction "2_2") (pintype "passive"))
    )
    (net (code "69") (name "Net-(C17-Pad2)") (class "Default")
      (node (ref "C17") (pin "2") (pinfunction "2_2") (pintype "passive"))
      (node (ref "D117") (pin "A") (pinfunction "A_A") (pintype "passive"))
      (node (ref "D120") (pin "C") (pinfunction "C_C") (pintype "passive"))
      (node (ref "R56") (pin "2") (pinfunction "2_2") (pintype "passive"))
    )
    (net (code "70") (name "Net-(C19-Pad1)") (class "Default")
      (node (ref "C19") (pin "1") (pinfunction "1_1") (pintype "passive"))
      (node (ref "D123") (pin "C") (pinfunction "C_C") (pintype "passive"))
      (node (ref "R60") (pin "2") (pinfunction "2_2") (pintype "passive"))
    )
    (net (code "71") (name "Net-(C19-Pad2)") (class "Default")
      (node (ref "C19") (pin "2") (pinfunction "2_2") (pintype "passive"))
      (node (ref "D125") (pin "A") (pinfunction "A_A") (pintype "passive"))
      (node (ref "D126") (pin "C") (pinfunction "C_C") (pintype "passive"))
      (node (ref "R62") (pin "2") (pinfunction "2_2") (pintype "passive"))
    )
    (net (code "72") (name "Net-(C20-Pad1)") (class "Default")
      (node (ref "C20") (pin "1") (pinfunction "1_1") (pintype "passive"))
      (node (ref "D129") (pin "C") (pinfunction "C_C") (pintype "passive"))
      (node (ref "R64") (pin "2") (pinfunction "2_2") (pintype "passive"))
    )
    (net (code "73") (name "Net-(C20-Pad2)") (class "Default")
      (node (ref "C20") (pin "2") (pinfunction "2_2") (pintype "passive"))
      (node (ref "D131") (pin "A") (pinfunction "A_A") (pintype "passive"))
      (node (ref "D132") (pin "C") (pinfunction "C_C") (pintype "passive"))
      (node (ref "R67") (pin "2") (pinfunction "2_2") (pintype "passive"))
    )
    (net (code "74") (name "Net-(D16-PadC)") (class "Default")
      (node (ref "D16") (pin "C") (pinfunction "C_C") (pintype "passive"))
      (node (ref "D32") (pin "A") (pinfunction "A_A") (pintype "passive"))
      (node (ref "D7") (pin "C") (pinfunction "C_C") (pintype "passive"))
    )
    (net (code "75") (name "Net-(D19-PadC)") (class "Default")
      (node (ref "D19") (pin "C") (pinfunction "C_C") (pintype "passive"))
      (node (ref "D33") (pin "C") (pinfunction "C_C") (pintype "passive"))
      (node (ref "D42") (pin "A") (pinfunction "A_A") (pintype "passive"))
      (node (ref "D5") (pin "C") (pinfunction "C_C") (pintype "passive"))
    )
    (net (code "76") (name "Net-(D20-PadC)") (class "Default")
      (node (ref "D20") (pin "C") (pinfunction "C_C") (pintype "passive"))
      (node (ref "D31") (pin "A") (pinfunction "A_A") (pintype "passive"))
      (node (ref "D6") (pin "C") (pinfunction "C_C") (pintype "passive"))
    )
    (net (code "77") (name "Net-(D30-PadC)") (class "Default")
      (node (ref "D30") (pin "C") (pinfunction "C_C") (pintype "passive"))
      (node (ref "D34") (pin "C") (pinfunction "C_C") (pintype "passive"))
      (node (ref "D39") (pin "C") (pinfunction "C_C") (pintype "passive"))
      (node (ref "R16") (pin "2") (pinfunction "2_2") (pintype "passive"))
    )
    (net (code "78") (name "Net-(D34-PadA)") (class "Default")
      (node (ref "D34") (pin "A") (pinfunction "A_A") (pintype "passive"))
      (node (ref "D35") (pin "C") (pinfunction "C_C") (pintype "passive"))
    )
    (net (code "79") (name "Net-(D40-PadC)") (class "Default")
      (node (ref "D40") (pin "C") (pinfunction "C_C") (pintype "passive"))
      (node (ref "D41") (pin "C") (pinfunction "C_C") (pintype "passive"))
      (node (ref "D44") (pin "C") (pinfunction "C_C") (pintype "passive"))
      (node (ref "D49") (pin "C") (pinfunction "C_C") (pintype "passive"))
      (node (ref "R21") (pin "2") (pinfunction "2_2") (pintype "passive"))
    )
    (net (code "80") (name "Net-(D43-PadC)") (class "Default")
      (node (ref "D43") (pin "C") (pinfunction "C_C") (pintype "passive"))
      (node (ref "D46") (pin "C") (pinfunction "C_C") (pintype "passive"))
      (node (ref "D53") (pin "C") (pinfunction "C_C") (pintype "passive"))
      (node (ref "R24") (pin "2") (pinfunction "2_2") (pintype "passive"))
    )
    (net (code "81") (name "Net-(D44-PadA)") (class "Default")
      (node (ref "D44") (pin "A") (pinfunction "A_A") (pintype "passive"))
      (node (ref "D45") (pin "C") (pinfunction "C_C") (pintype "passive"))
    )
    (net (code "82") (name "Net-(D46-PadA)") (class "Default")
      (node (ref "D46") (pin "A") (pinfunction "A_A") (pintype "passive"))
      (node (ref "D47") (pin "C") (pinfunction "C_C") (pintype "passive"))
    )
    (net (code "83") (name "Net-(D51-PadC)") (class "Default")
      (node (ref "D51") (pin "C") (pinfunction "C_C") (pintype "passive"))
      (node (ref "D54") (pin "C") (pinfunction "C_C") (pintype "passive"))
      (node (ref "R27") (pin "2") (pinfunction "2_2") (pintype "passive"))
    )
    (net (code "84") (name "Net-(D54-PadA)") (class "Default")
      (node (ref "D54") (pin "A") (pinfunction "A_A") (pintype "passive"))
      (node (ref "D55") (pin "C") (pinfunction "C_C") (pintype "passive"))
    )
    (net (code "85") (name "Net-(D56-PadA)") (class "Default")
      (node (ref "D56") (pin "A") (pinfunction "A_A") (pintype "passive"))
      (node (ref "D72") (pin "C") (pinfunction "C_C") (pintype "passive"))
      (node (ref "D83") (pin "C") (pinfunction "C_C") (pintype "passive"))
      (node (ref "D99") (pin "C") (pinfunction "C_C") (pintype "passive"))
    )
    (net (code "86") (name "Net-(D58-PadC)") (class "Default")
      (node (ref "D58") (pin "C") (pinfunction "C_C") (pintype "passive"))
      (node (ref "D64") (pin "C") (pinfunction "C_C") (pintype "passive"))
      (node (ref "D69") (pin "C") (pinfunction "C_C") (pintype "passive"))
      (node (ref "R33") (pin "2") (pinfunction "2_2") (pintype "passive"))
    )
    (net (code "87") (name "Net-(D62-PadC)") (class "Default")
      (node (ref "D62") (pin "C") (pinfunction "C_C") (pintype "passive"))
      (node (ref "D67") (pin "C") (pinfunction "C_C") (pintype "passive"))
      (node (ref "D70") (pin "C") (pinfunction "C_C") (pintype "passive"))
      (node (ref "R35") (pin "2") (pinfunction "2_2") (pintype "passive"))
    )
    (net (code "88") (name "Net-(D64-PadA)") (class "Default")
      (node (ref "D64") (pin "A") (pinfunction "A_A") (pintype "passive"))
      (node (ref "D65") (pin "C") (pinfunction "C_C") (pintype "passive"))
    )
    (net (code "89") (name "Net-(D67-PadA)") (class "Default")
      (node (ref "D67") (pin "A") (pinfunction "A_A") (pintype "passive"))
      (node (ref "D68") (pin "C") (pinfunction "C_C") (pintype "passive"))
    )
    (net (code "90") (name "Net-(D102-PadC)") (class "Default")
      (node (ref "D102") (pin "C") (pinfunction "C_C") (pintype "passive"))
      (node (ref "D117") (pin "C") (pinfunction "C_C") (pintype "passive"))
      (node (ref "D125") (pin "C") (pinfunction "C_C") (pintype "passive"))
      (node (ref "D131") (pin "C") (pinfunction "C_C") (pintype "passive"))
      (node (ref "D93") (pin "A") (pinfunction "A_A") (pintype "passive"))
    )
    (net (code "91") (name "Net-(D105-PadC)") (class "Default")
      (node (ref "D105") (pin "C") (pinfunction "C_C") (pintype "passive"))
      (node (ref "D71") (pin "A") (pinfunction "A_A") (pintype "passive"))
      (node (ref "D82") (pin "C") (pinfunction "C_C") (pintype "passive"))
      (node (ref "D94") (pin "C") (pinfunction "C_C") (pintype "passive"))
    )
    (net (code "92") (name "Net-(D110-PadA)") (class "Default")
      (node (ref "D110") (pin "A") (pinfunction "A_A") (pintype "passive"))
      (node (ref "D111") (pin "C") (pinfunction "C_C") (pintype "passive"))
    )
    (net (code "93") (name "Net-(D111-PadA)") (class "Default")
      (node (ref "D111") (pin "A") (pinfunction "A_A") (pintype "passive"))
      (node (ref "D112") (pin "C") (pinfunction "C_C") (pintype "passive"))
    )
    (net (code "94") (name "Net-(D116-PadC)") (class "Default")
      (node (ref "D116") (pin "C") (pinfunction "C_C") (pintype "passive"))
      (node (ref "D118") (pin "C") (pinfunction "C_C") (pintype "passive"))
      (node (ref "R57") (pin "2") (pinfunction "2_2") (pintype "passive"))
    )
    (net (code "95") (name "Net-(D118-PadA)") (class "Default")
      (node (ref "D118") (pin "A") (pinfunction "A_A") (pintype "passive"))
      (node (ref "D119") (pin "C") (pinfunction "C_C") (pintype "passive"))
    )
    (net (code "96") (name "Net-(Q1-B)") (class "Default")
      (node (ref "C7") (pin "2") (pinfunction "2_2") (pintype "passive"))
      (node (ref "D28") (pin "C") (pinfunction "C_C") (pintype "passive"))
      (node (ref "D36") (pin "C") (pinfunction "C_C") (pintype "passive"))
      (node (ref "Q1") (pin "2") (pinfunction "B_2") (pintype "passive"))
      (node (ref "R15") (pin "2") (pinfunction "2_2") (pintype "passive"))
    )
    (net (code "97") (name "Net-(Q1-C)") (class "Default")
      (node (ref "Q1") (pin "3") (pinfunction "C_3") (pintype "passive"))
      (node (ref "R19") (pin "1") (pinfunction "1_1") (pintype "passive"))
    )
    (net (code "98") (name "Net-(Q1-E)") (class "Default")
      (node (ref "D32") (pin "C") (pinfunction "C_C") (pintype "passive"))
      (node (ref "D47") (pin "A") (pinfunction "A_A") (pintype "passive"))
      (node (ref "Q1") (pin "1") (pinfunction "E_1") (pintype "passive"))
      (node (ref "Q5") (pin "2") (pinfunction "B_2") (pintype "passive"))
      (node (ref "R25") (pin "1") (pinfunction "1_1") (pintype "passive"))
    )
    (net (code "99") (name "Net-(Q2-B)") (class "Default")
      (node (ref "D31") (pin "C") (pinfunction "C_C") (pintype "passive"))
      (node (ref "D35") (pin "A") (pinfunction "A_A") (pintype "passive"))
      (node (ref "Q2") (pin "2") (pinfunction "B_2") (pintype "passive"))
      (node (ref "R17") (pin "1") (pinfunction "1_1") (pintype "passive"))
    )
    (net (code "100") (name "Net-(Q3-B)") (class "Default")
      (node (ref "D55") (pin "A") (pinfunction "A_A") (pintype "passive"))
      (node (ref "D56") (pin "C") (pinfunction "C_C") (pintype "passive"))
      (node (ref "Q3") (pin "2") (pinfunction "B_2") (pintype "passive"))
      (node (ref "R28") (pin "1") (pinfunction "1_1") (pintype "passive"))
    )
    (net (code "101") (name "Net-(Q4-B)") (class "Default")
      (node (ref "D42") (pin "C") (pinfunction "C_C") (pintype "passive"))
      (node (ref "D45") (pin "A") (pinfunction "A_A") (pintype "passive"))
      (node (ref "Q4") (pin "2") (pinfunction "B_2") (pintype "passive"))
      (node (ref "R22") (pin "1") (pinfunction "1_1") (pintype "passive"))
    )
    (net (code "102") (name "Net-(Q6-B)") (class "Default")
      (node (ref "D65") (pin "A") (pinfunction "A_A") (pintype "passive"))
      (node (ref "D71") (pin "C") (pinfunction "C_C") (pintype "passive"))
      (node (ref "Q6") (pin "2") (pinfunction "B_2") (pintype "passive"))
      (node (ref "R34") (pin "1") (pinfunction "1_1") (pintype "passive"))
    )
    (net (code "103") (name "Net-(Q7-B)") (class "Default")
      (node (ref "D68") (pin "A") (pinfunction "A_A") (pintype "passive"))
      (node (ref "D93") (pin "C") (pinfunction "C_C") (pintype "passive"))
      (node (ref "Q7") (pin "2") (pinfunction "B_2") (pintype "passive"))
      (node (ref "Q8") (pin "1") (pinfunction "E_1") (pintype "passive"))
      (node (ref "R36") (pin "1") (pinfunction "1_1") (pintype "passive"))
    )
    (net (code "104") (name "Net-(Q8-B)") (class "Default")
      (node (ref "C12") (pin "2") (pinfunction "2_2") (pintype "passive"))
      (node (ref "D85") (pin "C") (pinfunction "C_C") (pintype "passive"))
      (node (ref "D88") (pin "C") (pinfunction "C_C") (pintype "passive"))
      (node (ref "Q8") (pin "2") (pinfunction "B_2") (pintype "passive"))
      (node (ref "R44") (pin "2") (pinfunction "2_2") (pintype "passive"))
    )
    (net (code "105") (name "Net-(Q8-C)") (class "Default")
      (node (ref "Q8") (pin "3") (pinfunction "C_3") (pintype "passive"))
      (node (ref "R48") (pin "2") (pinfunction "2_2") (pintype "passive"))
    )
    (net (code "106") (name "Net-(Q9-B)") (class "Default")
      (node (ref "D119") (pin "A") (pinfunction "A_A") (pintype "passive"))
      (node (ref "Q9") (pin "2") (pinfunction "B_2") (pintype "passive"))
      (node (ref "R58") (pin "1") (pinfunction "1_1") (pintype "passive"))
    )
    (net (code "107") (name "Net-(Q9-C)") (class "Default")
      (node (ref "D11") (pin "A") (pinfunction "A_A") (pintype "passive"))
      (node (ref "D122") (pin "C") (pinfunction "C_C") (pintype "passive"))
      (node (ref "D8") (pin "A") (pinfunction "A_A") (pintype "passive"))
      (node (ref "Q9") (pin "3") (pinfunction "C_3") (pintype "passive"))
      (node (ref "R59") (pin "2") (pinfunction "2_2") (pintype "passive"))
    )
    (net (code "108") (name "Net-(Q10-B)") (class "Default")
      (node (ref "C23") (pin "1") (pinfunction "1_1") (pintype "passive"))
      (node (ref "Q10") (pin "2") (pinfunction "B_2") (pintype "passive"))
      (node (ref "R66") (pin "1") (pinfunction "1_1") (pintype "passive"))
    )
    (net (code "109") (name "Net-(Q11-B)") (class "Default")
      (node (ref "C24") (pin "1") (pinfunction "1_1") (pintype "passive"))
      (node (ref "Q11") (pin "2") (pinfunction "B_2") (pintype "passive"))
      (node (ref "R72") (pin "1") (pinfunction "1_1") (pintype "passive"))
    )
    (net (code "110") (name "Net-(Q12-B)") (class "Default")
      (node (ref "C21") (pin "1") (pinfunction "1_1") (pintype "passive"))
      (node (ref "Q12") (pin "2") (pinfunction "B_2") (pintype "passive"))
      (node (ref "R70") (pin "1") (pinfunction "1_1") (pintype "passive"))
    )
    (net (code "111") (name "Net-(Q13-B)") (class "Default")
      (node (ref "C22") (pin "1") (pinfunction "1_1") (pintype "passive"))
      (node (ref "Q13") (pin "2") (pinfunction "B_2") (pintype "passive"))
      (node (ref "R74") (pin "1") (pinfunction "1_1") (pintype "passive"))
    )
    (net (code "112") (name "Net-(U$1AB-1)") (class "Default")
      (node (ref "D108") (pin "A") (pinfunction "A_A") (pintype "passive"))
      (node (ref "D109") (pin "A") (pinfunction "A_A") (pintype "passive"))
      (node (ref "D116") (pin "A") (pinfunction "A_A") (pintype "passive"))
      (node (ref "D137") (pin "C") (pinfunction "C_C") (pintype "passive"))
      (node (ref "R61") (pin "2") (pinfunction "2_2") (pintype "passive"))
      (node (ref "U$1") (pin "AR2") (pinfunction "1_AR2") (pintype "bidirectional"))
    )
    (net (code "113") (name "Net-(U$1BJ-1)") (class "Default")
      (node (ref "D126") (pin "A") (pinfunction "A_A") (pintype "passive"))
      (node (ref "D128") (pin "A") (pinfunction "A_A") (pintype "passive"))
      (node (ref "U$1") (pin "BP2") (pinfunction "1_BP2") (pintype "bidirectional"))
    )
    (net (code "114") (name "Net-(U$1BL-1)") (class "Default")
      (node (ref "D1") (pin "A") (pinfunction "A_A") (pintype "passive"))
      (node (ref "D10") (pin "A") (pinfunction "A_A") (pintype "passive"))
      (node (ref "U$1") (pin "BR2") (pinfunction "1_BR2") (pintype "bidirectional"))
    )
  )
)
